# rev_n_v28.net
KiCad netlist of a schematic drawn in EAGLE
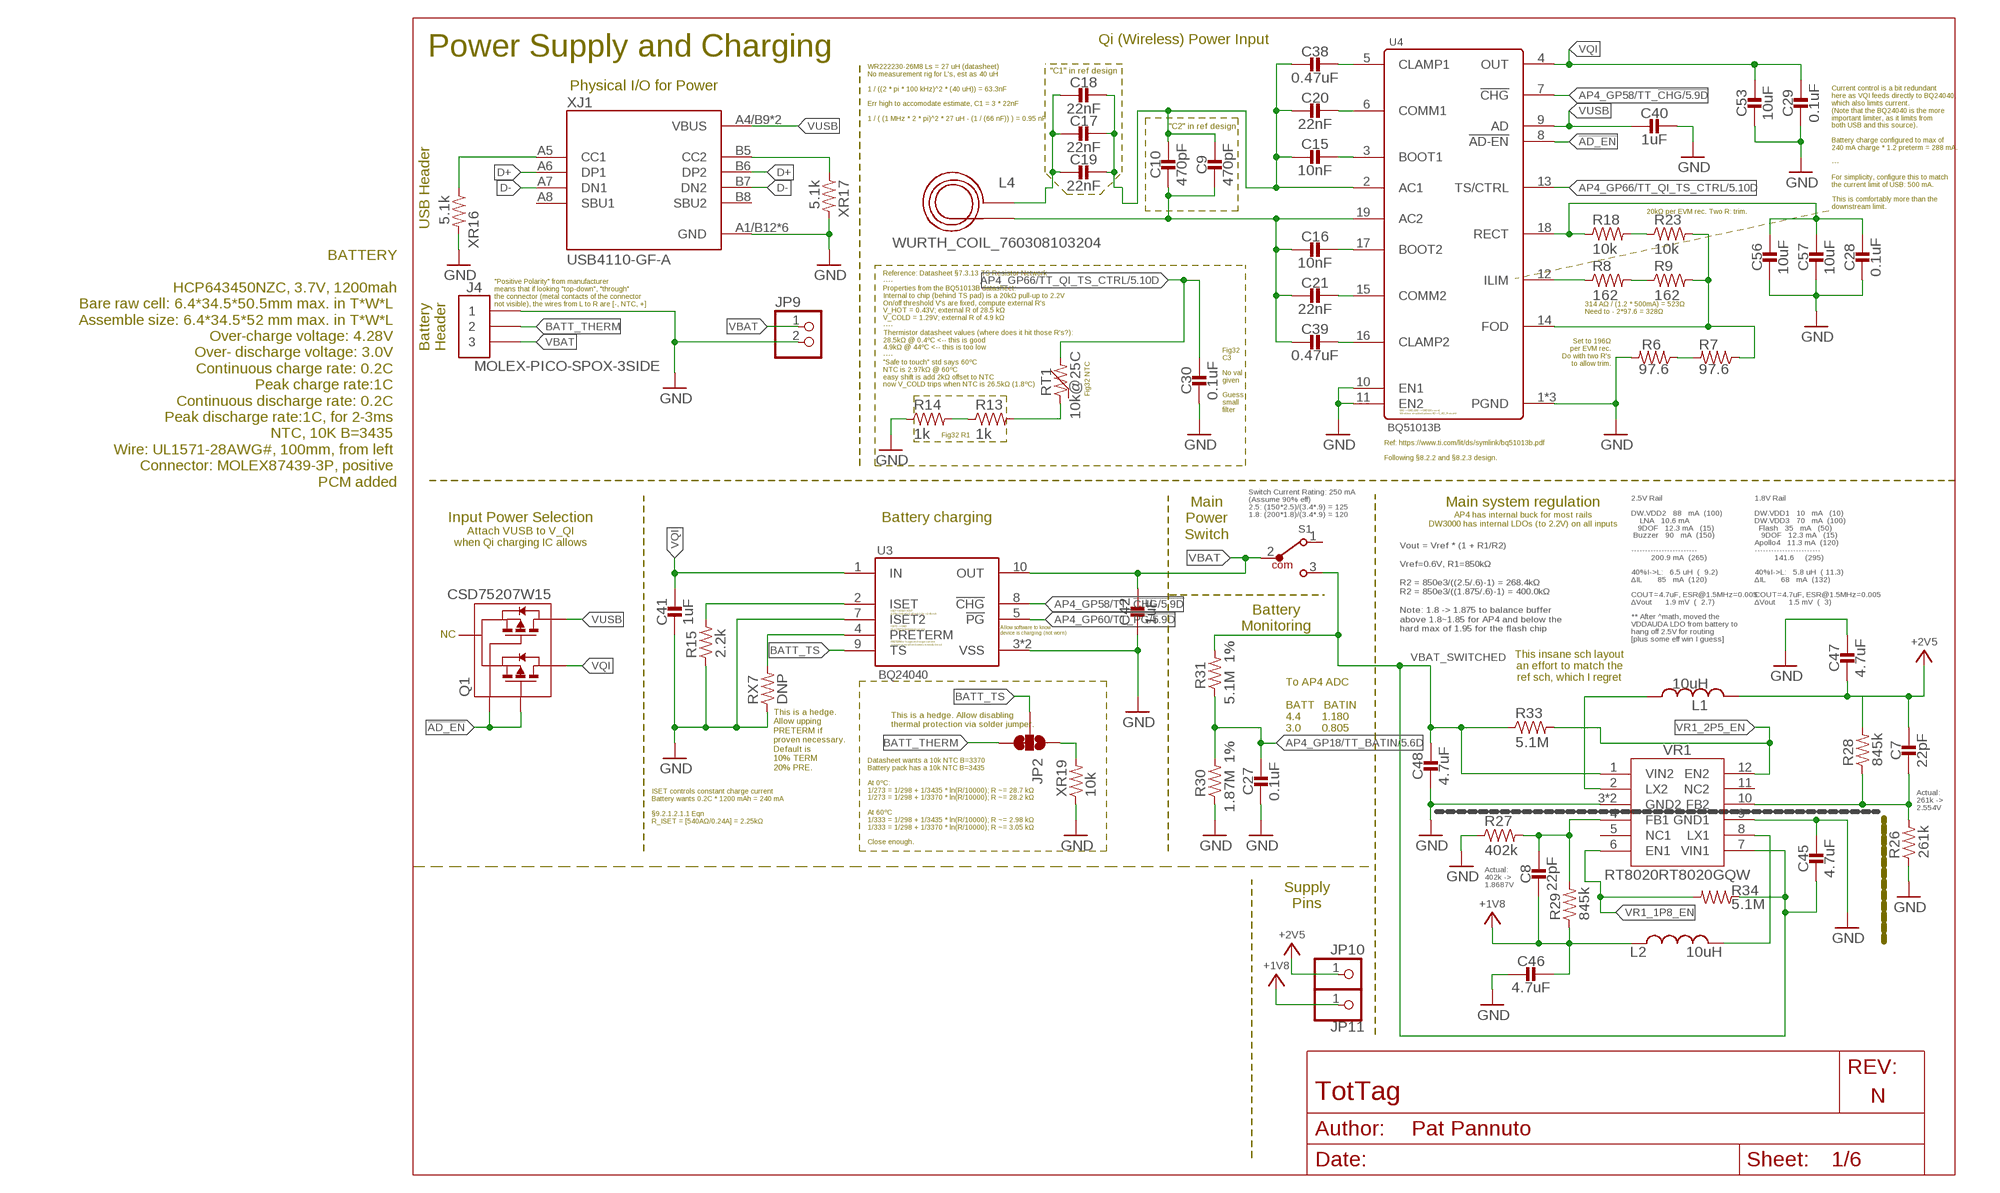
[diagram p0: schematic, sheet 1]
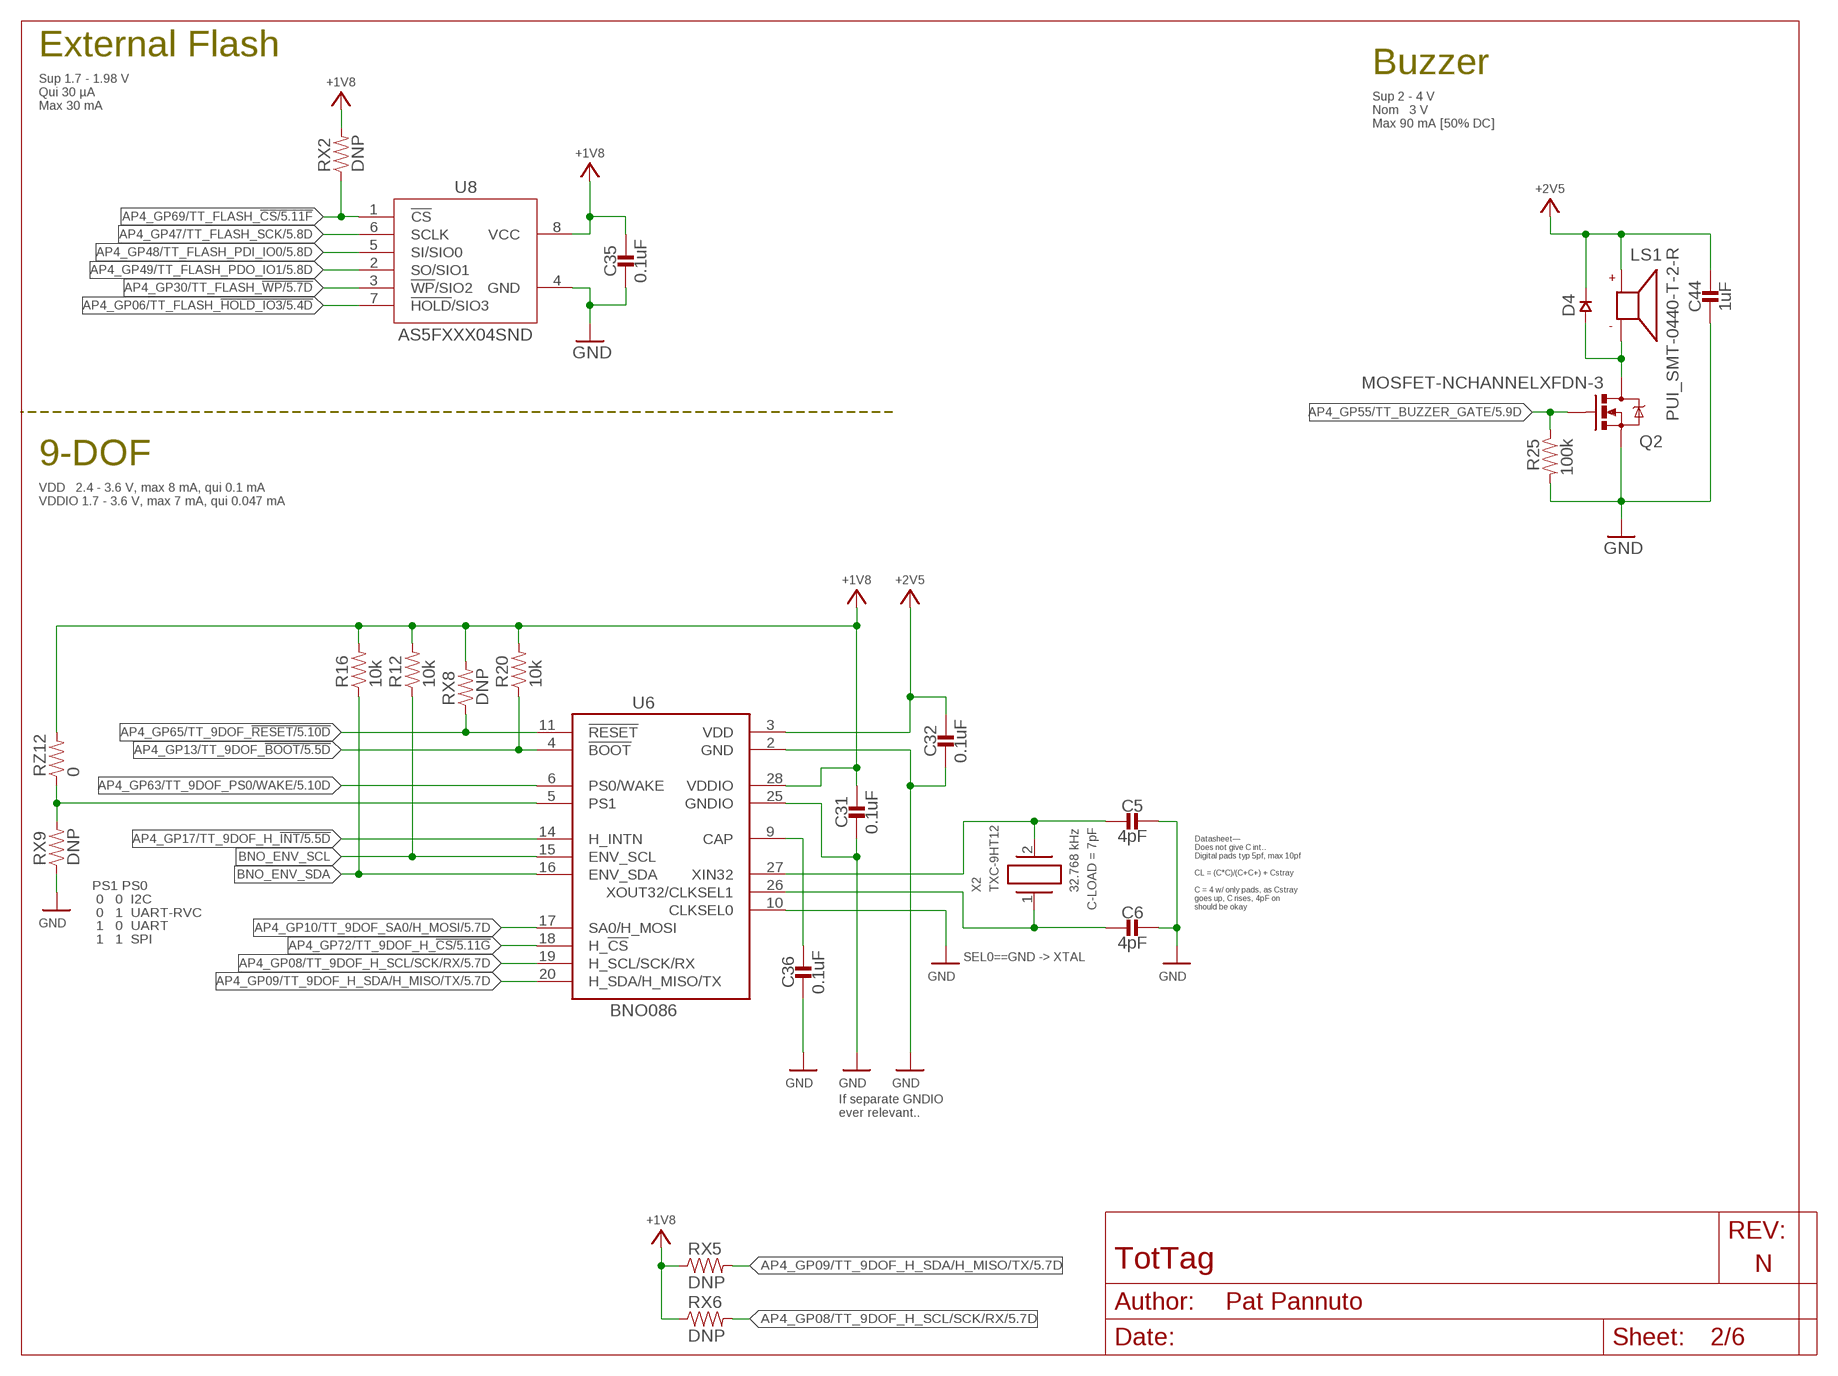
[diagram p1: schematic, sheet 2]
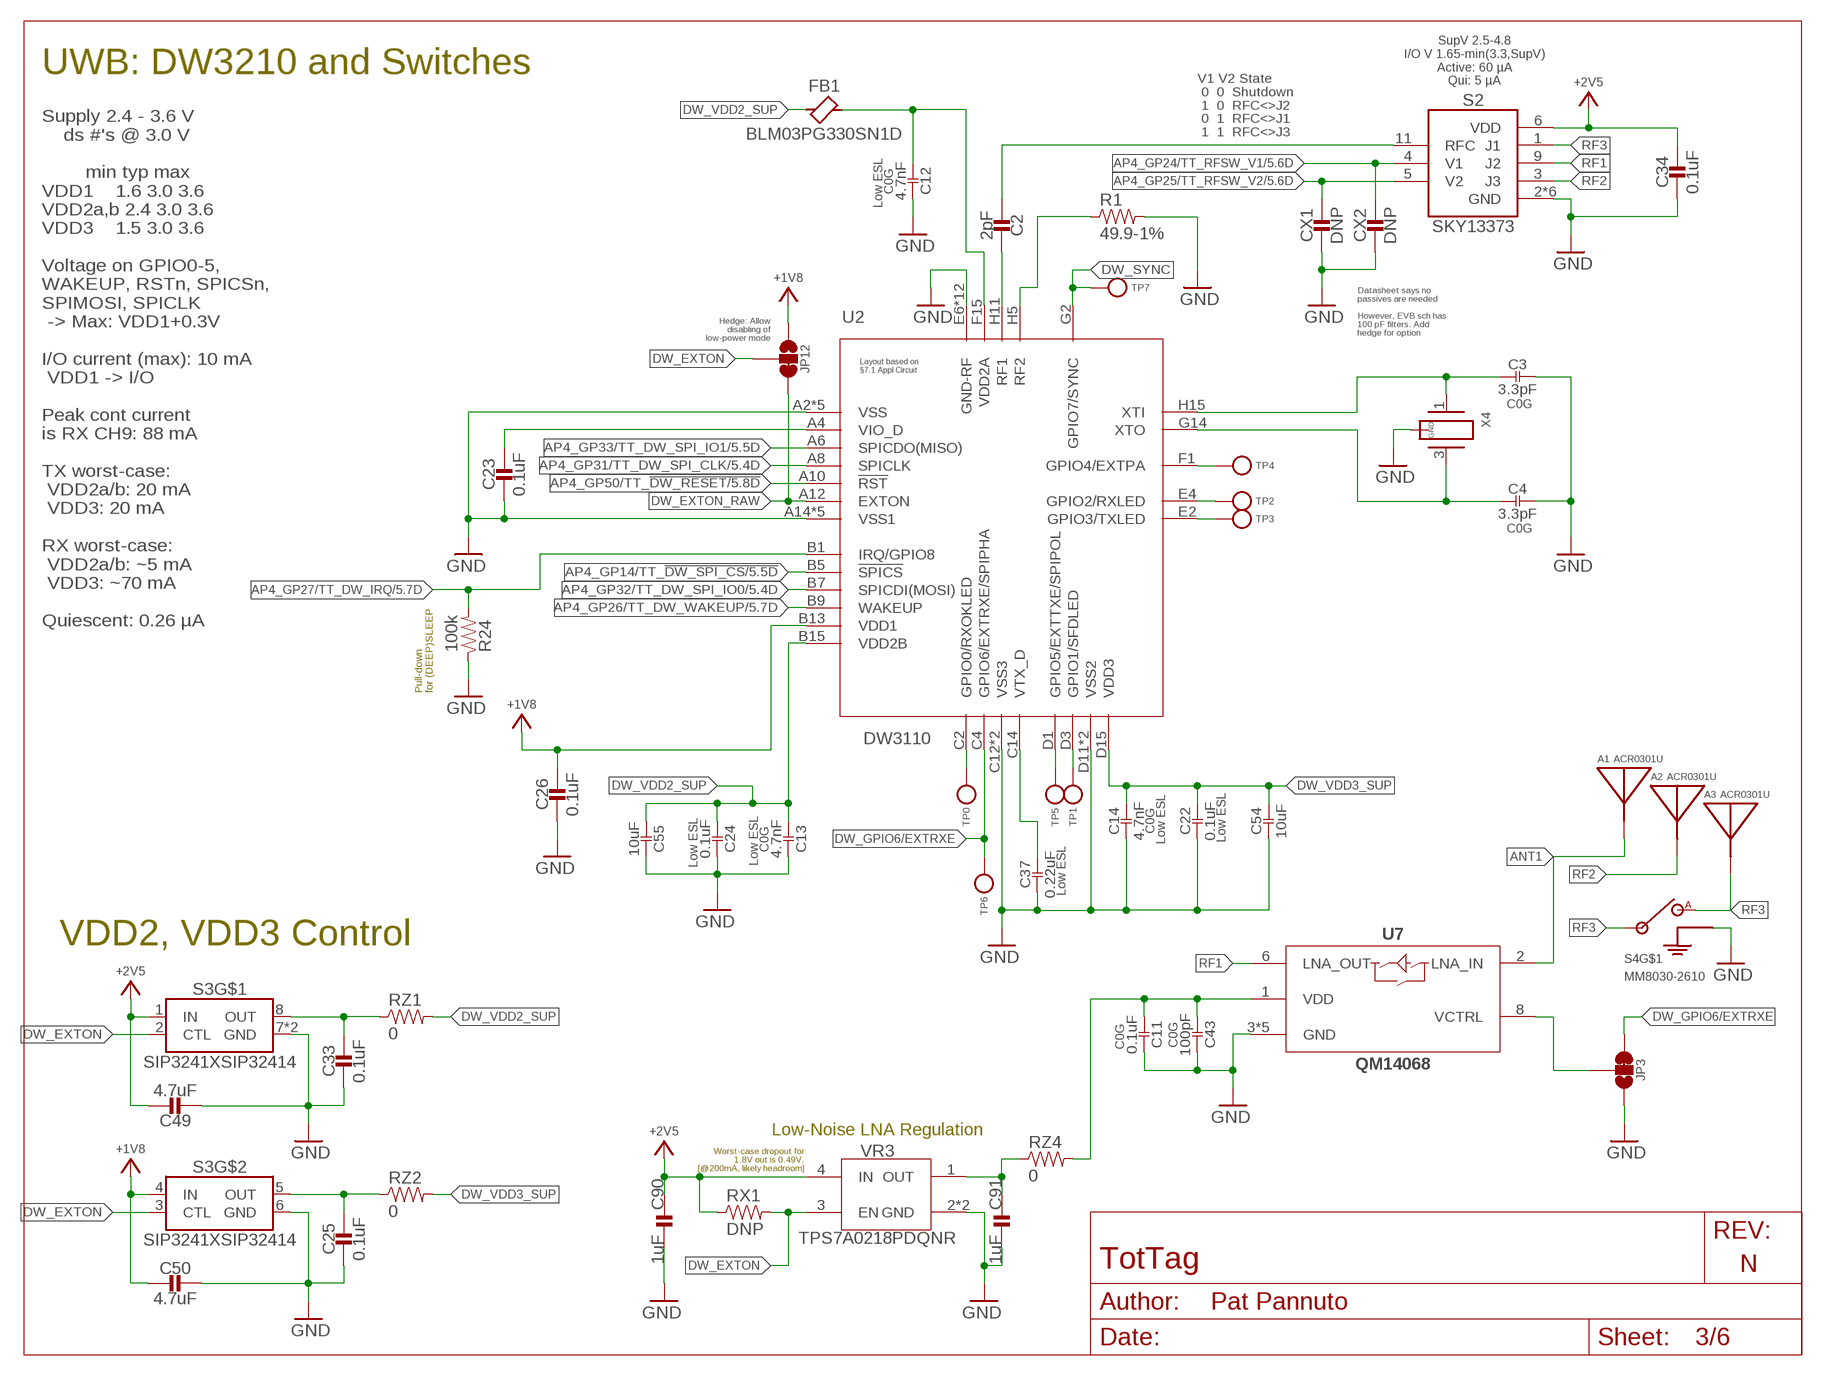
[diagram p2: schematic, sheet 3]
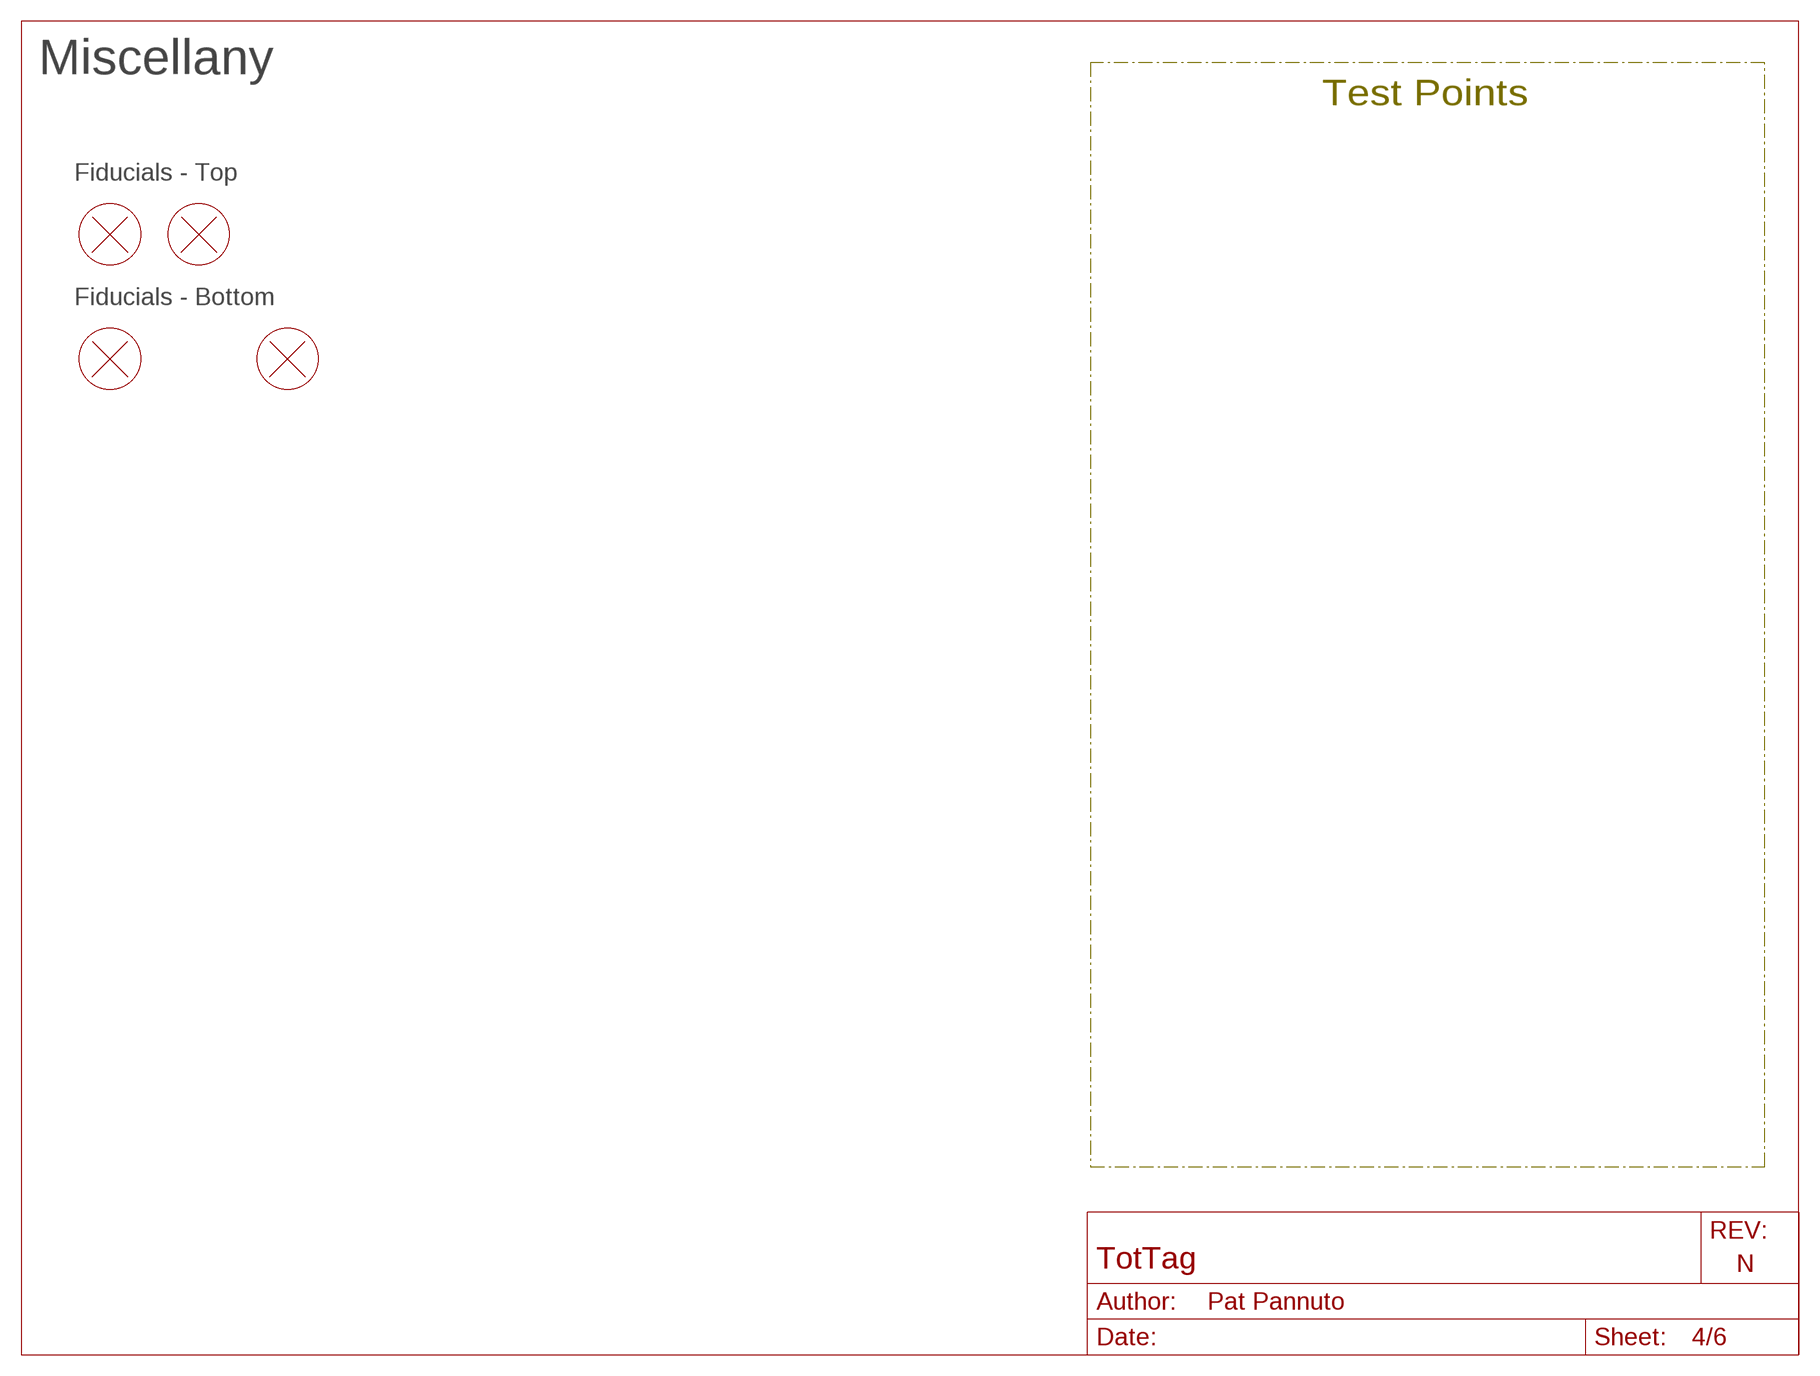
[diagram p3: schematic, sheet 4]
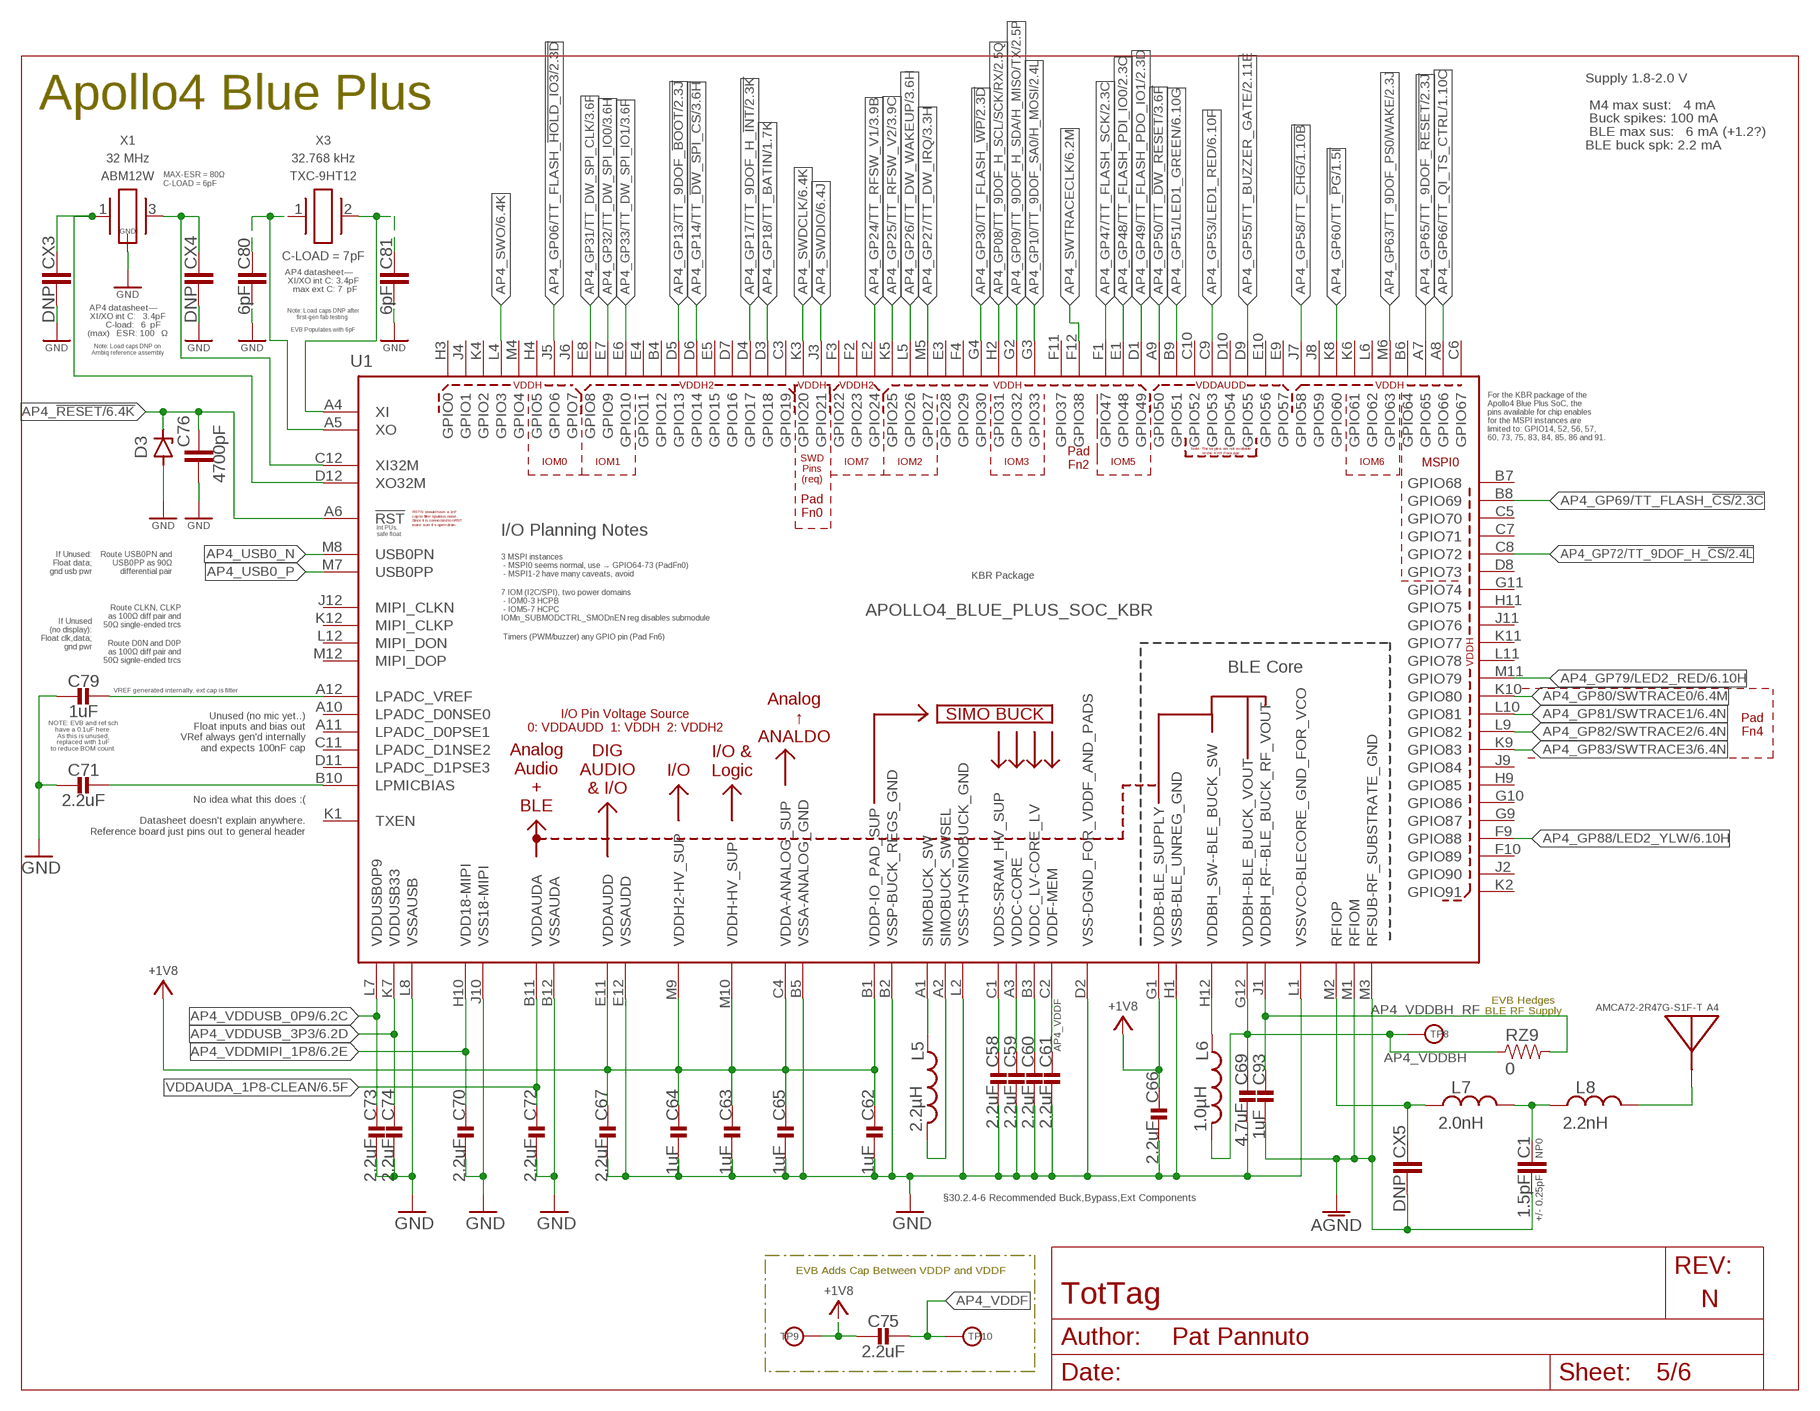
[diagram p4: schematic, sheet 5]
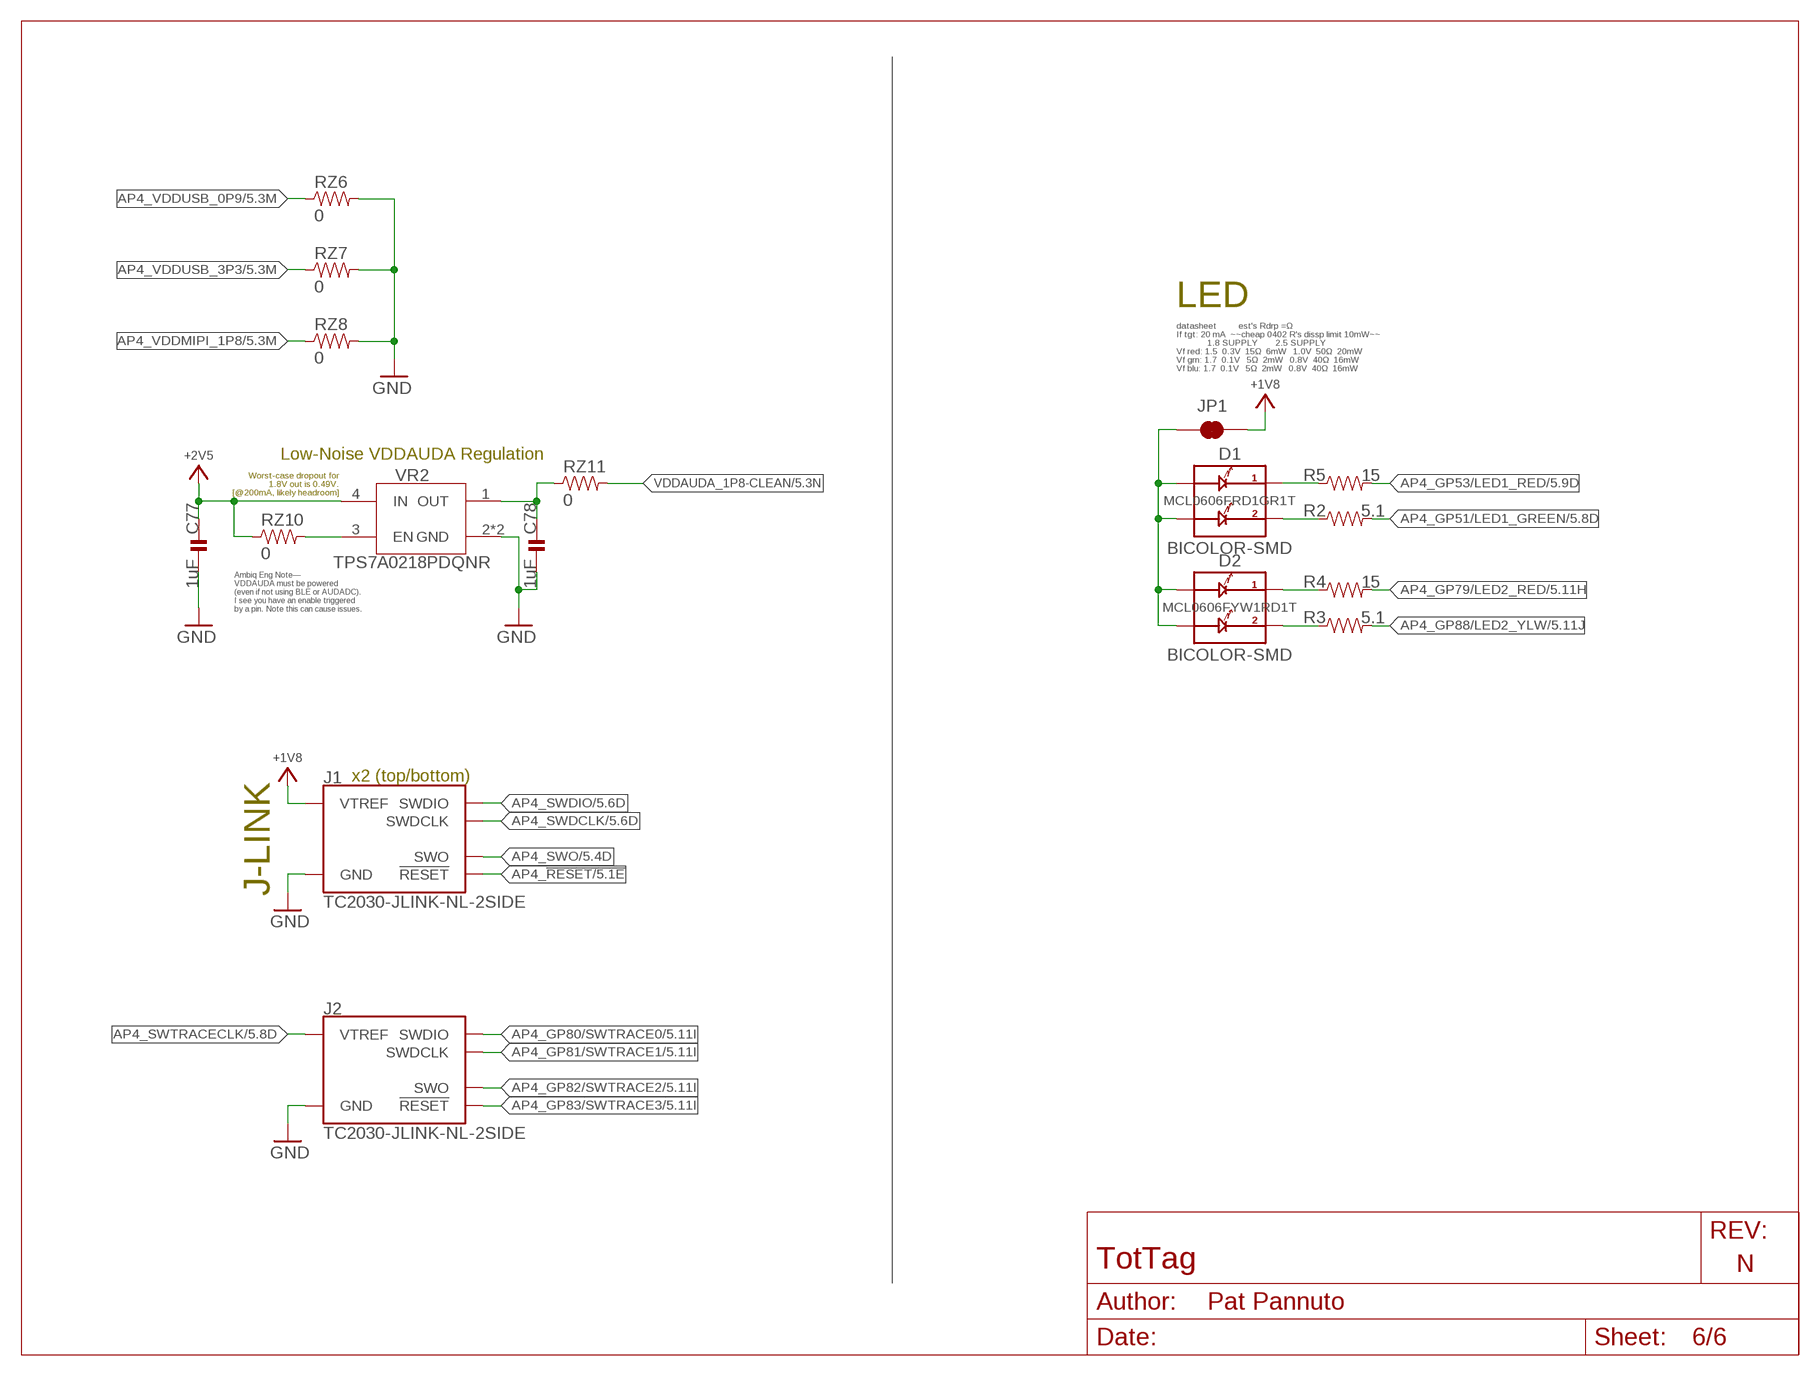
[diagram p5: schematic, sheet 6]

(export (version "E")
  (design (tool "Eeschema 10.0.6"))
  (components
    (comp (ref "A1")
      (value "ACR0301U")
      (footprint "eagle-import:ACR0301U")
      (fields (field (name "MANUFACTURER") "Abracon"))
      (libsource (lib "eagle-import") (part "ACR0301U"))
    )
    (comp (ref "A2")
      (value "ACR0301U")
      (footprint "eagle-import:ACR0301U")
      (fields (field (name "MANUFACTURER") "Abracon"))
      (libsource (lib "eagle-import") (part "ACR0301U"))
    )
    (comp (ref "A3")
      (value "ACR0301U")
      (footprint "eagle-import:ACR0301U")
      (fields (field (name "MANUFACTURER") "Abracon"))
      (libsource (lib "eagle-import") (part "ACR0301U"))
    )
    (comp (ref "C2")
      (value "2pF")
      (footprint "eagle-import:0201_CAP")
      (fields (field (name "MPN") "CBR02C209A5GAC"))
      (libsource (lib "eagle-import") (part "CAPACITOR0201_CAP"))
    )
    (comp (ref "C3")
      (value "3.3pF")
      (footprint "eagle-import:SMD_2012M-0805US-C")
      (fields
        (field (name "EIA") "C0G")
        (field (name "MANUFACTURER") "KYOCERA AVX")
        (field (name "MPN") "600F3R3BT250XT")
      )
      (libsource (lib "eagle-import") (part "C0805US"))
    )
    (comp (ref "C4")
      (value "3.3pF")
      (footprint "eagle-import:SMD_2012M-0805US-C")
      (fields
        (field (name "EIA") "C0G")
        (field (name "MANUFACTURER") "KYOCERA AVX")
        (field (name "MPN") "600F3R3BT250XT")
      )
      (libsource (lib "eagle-import") (part "C0805US"))
    )
    (comp (ref "C11")
      (value "0.1uF")
      (footprint "eagle-import:SMD_3216M-1206US-C")
      (fields (field (name "EIA") "C0G") (field (name "MPN") "GRM31C5C1H104JA01L"))
      (libsource (lib "eagle-import") (part "C1206US"))
    )
    (comp (ref "C12")
      (value "4.7nF")
      (footprint "eagle-import:SMD_1608M-0603US-C")
      (fields
        (field (name "EIA") "C0G")
        (field (name "FEATURES") "Low ESL")
        (field (name "MANUFACTURER") "KEMET")
        (field (name "MPN") "C0603C472J5GAC7867")
      )
      (libsource (lib "eagle-import") (part "C0603US"))
    )
    (comp (ref "C13")
      (value "4.7nF")
      (footprint "eagle-import:SMD_1608M-0603US-C")
      (fields
        (field (name "EIA") "C0G")
        (field (name "FEATURES") "Low ESL")
        (field (name "MANUFACTURER") "KEMET")
        (field (name "MPN") "C0603C472J5GAC7867")
      )
      (libsource (lib "eagle-import") (part "C0603US"))
    )
    (comp (ref "C14")
      (value "4.7nF")
      (footprint "eagle-import:SMD_1608M-0603US-C")
      (fields
        (field (name "EIA") "C0G")
        (field (name "FEATURES") "Low ESL")
        (field (name "MANUFACTURER") "KEMET")
        (field (name "MPN") "C0603C472J5GAC7867")
      )
      (libsource (lib "eagle-import") (part "C0603US"))
    )
    (comp (ref "C22")
      (value "0.1uF")
      (footprint "eagle-import:SMD_1608M-0603US-C")
      (fields (field (name "FEATURES") "Low ESL") (field (name "MPN") "C1608X7R1H104K080AA"))
      (libsource (lib "eagle-import") (part "C0603US"))
    )
    (comp (ref "C23")
      (value "0.1uF")
      (footprint "eagle-import:0402_CAP")
      (fields (field (name "MPN") "CL05A104KP5NNNC"))
      (libsource (lib "eagle-import") (part "passives_20904581_CAPACITOR0402_CAP"))
    )
    (comp (ref "C24")
      (value "0.1uF")
      (footprint "eagle-import:SMD_1608M-0603US-C")
      (fields (field (name "FEATURES") "Low ESL") (field (name "MPN") "C1608X7R1H104K080AA"))
      (libsource (lib "eagle-import") (part "C0603US"))
    )
    (comp (ref "C25")
      (value "0.1uF")
      (footprint "eagle-import:0402_CAP")
      (fields (field (name "MPN") "CL05A104KP5NNNC"))
      (libsource (lib "eagle-import") (part "passives_20904581_CAPACITOR0402_CAP"))
    )
    (comp (ref "C26")
      (value "0.1uF")
      (footprint "eagle-import:0402_CAP")
      (fields (field (name "MPN") "CL05A104KP5NNNC"))
      (libsource (lib "eagle-import") (part "passives_20904581_CAPACITOR0402_CAP"))
    )
    (comp (ref "C33")
      (value "0.1uF")
      (footprint "eagle-import:0402_CAP")
      (fields (field (name "MPN") "CL05A104KP5NNNC"))
      (libsource (lib "eagle-import") (part "passives_20904581_CAPACITOR0402_CAP"))
    )
    (comp (ref "C34")
      (value "0.1uF")
      (footprint "eagle-import:0402_CAP")
      (fields (field (name "MPN") "CL05A104KP5NNNC"))
      (libsource (lib "eagle-import") (part "passives_20904581_CAPACITOR0402_CAP"))
    )
    (comp (ref "C37")
      (value "0.22uF")
      (footprint "eagle-import:SMD_1608M-0603US-C")
      (fields (field (name "FEATURES") "Low ESL") (field (name "MPN") "C1608X7R1H224K080AB"))
      (libsource (lib "eagle-import") (part "C0603US"))
    )
    (comp (ref "C43")
      (value "100pF")
      (footprint "eagle-import:SMD_1005M-0402US-C")
      (fields (field (name "EIA") "C0G") (field (name "MPN") "C0402C101J3GACTU"))
      (libsource (lib "eagle-import") (part "C0402US"))
    )
    (comp (ref "C49")
      (value "4.7uF")
      (footprint "eagle-import:0603_CAP")
      (fields (field (name "MPN") "C1608X7S1A475K080AC"))
      (libsource (lib "eagle-import") (part "passives_20904581_CAPACITOR0603_CAP"))
    )
    (comp (ref "C50")
      (value "4.7uF")
      (footprint "eagle-import:0603_CAP")
      (fields (field (name "MPN") "C1608X7S1A475K080AC"))
      (libsource (lib "eagle-import") (part "passives_20904581_CAPACITOR0603_CAP"))
    )
    (comp (ref "C54")
      (value "10uF")
      (footprint "eagle-import:SMD_1608M-0603US-C")
      (fields (field (name "MPN") "CM105X5R106M25AT"))
      (libsource (lib "eagle-import") (part "C0603US"))
    )
    (comp (ref "C55")
      (value "10uF")
      (footprint "eagle-import:SMD_1608M-0603US-C")
      (fields (field (name "MPN") "CM105X5R106M25AT"))
      (libsource (lib "eagle-import") (part "C0603US"))
    )
    (comp (ref "C90")
      (value "1uF")
      (footprint "eagle-import:0201_CAP")
      (fields (field (name "MANUFACTURER") "Murata") (field (name "MPN") "GRM033R61A105ME44D"))
      (libsource (lib "eagle-import") (part "passives_20904581_CAPACITOR0201_CAP"))
    )
    (comp (ref "C91")
      (value "1uF")
      (footprint "eagle-import:0201_CAP")
      (fields (field (name "MANUFACTURER") "Murata") (field (name "MPN") "GRM033R61A105ME44D"))
      (libsource (lib "eagle-import") (part "passives_20904581_CAPACITOR0201_CAP"))
    )
    (comp (ref "CX1")
      (value "DNP")
      (footprint "eagle-import:0603_CAP")
      (libsource (lib "eagle-import") (part "passives_20904581_CAPACITOR0603_CAP"))
    )
    (comp (ref "CX2")
      (value "DNP")
      (footprint "eagle-import:0603_CAP")
      (libsource (lib "eagle-import") (part "passives_20904581_CAPACITOR0603_CAP"))
    )
    (comp (ref "FB1")
      (value "BLM03PG330SN1D")
      (footprint "eagle-import:0201_FB")
      (fields (field (name "MANUFACTURER") "Murata"))
      (libsource (lib "eagle-import") (part "FERRITE_BEAD0201"))
    )
    (comp (ref "JP3")
      (value "JUMPER-SMT_3_1-NC_TRACE_SILK")
      (footprint "eagle-import:SMT-JUMPER_3_1-NC_TRACE_SILK")
      (libsource (lib "eagle-import") (part "JUMPER-SMT_3_1-NC_TRACE_SILK"))
    )
    (comp (ref "JP12")
      (value "JUMPER-SMT_3_1-NC_TRACE_SILK")
      (footprint "eagle-import:SMT-JUMPER_3_1-NC_TRACE_SILK")
      (libsource (lib "eagle-import") (part "JUMPER-SMT_3_1-NC_TRACE_SILK"))
    )
    (comp (ref "R1")
      (value "49.9-1%")
      (footprint "eagle-import:0201_RES")
      (fields (field (name "MPN") "ERJ-1GNF49R9C"))
      (libsource (lib "eagle-import") (part "passives_20904581_RESISTOR0201_RES"))
    )
    (comp (ref "R24")
      (value "100k")
      (footprint "eagle-import:0402_RES")
      (fields (field (name "MPN") "RT0402BRE07100KL"))
      (libsource (lib "eagle-import") (part "RESISTOR0402_RES"))
    )
    (comp (ref "RX1")
      (value "DNP")
      (footprint "eagle-import:0603-RES")
      (libsource (lib "eagle-import") (part "passives_20904581_RESISTOR0603_RES"))
    )
    (comp (ref "RZ1")
      (value "0")
      (footprint "eagle-import:0603-RES")
      (fields (field (name "MPN") "RMCF0603ZT0R00"))
      (libsource (lib "eagle-import") (part "passives_20904581_RESISTOR0603_RES"))
    )
    (comp (ref "RZ2")
      (value "0")
      (footprint "eagle-import:0603-RES")
      (fields (field (name "MPN") "RMCF0603ZT0R00"))
      (libsource (lib "eagle-import") (part "passives_20904581_RESISTOR0603_RES"))
    )
    (comp (ref "RZ4")
      (value "0")
      (footprint "eagle-import:0402_RES")
      (fields (field (name "MPN") "RMCF0402ZT0R00"))
      (libsource (lib "eagle-import") (part "passives_20904581_RESISTOR0402_RES"))
    )
    (comp (ref "S2")
      (value "SKY13373")
      (footprint "eagle-import:SKY13373")
      (fields (field (name "MANUFACTURER") "Skyworks") (field (name "MPN") "SKY13373-460LF"))
      (libsource (lib "eagle-import") (part "SKY13373"))
    )
    (comp (ref "S3")
      (value "SIP3241XSIP32414")
      (footprint "eagle-import:TDFN2X2X0P6-8")
      (fields (field (name "MANUFACTURER") "Vishay") (field (name "MPN") "SIP32414DNP-T1-GE4"))
      (libsource (lib "eagle-import") (part "SIP3241XSIP32414"))
    )
    (comp (ref "S4")
      (value "MM8030-2610")
      (footprint "eagle-import:MM8030-2610")
      (fields (field (name "MANUFACTURER") "Murata"))
      (libsource (lib "eagle-import") (part "MM8030-2610"))
    )
    (comp (ref "TP0")
      (value "TEST-POINT")
      (footprint "eagle-import:PAD.03X.03")
      (libsource (lib "eagle-import") (part "TEST-POINT"))
    )
    (comp (ref "TP1")
      (value "TEST-POINT")
      (footprint "eagle-import:PAD.03X.03")
      (libsource (lib "eagle-import") (part "TEST-POINT"))
    )
    (comp (ref "TP2")
      (value "TEST-POINT")
      (footprint "eagle-import:PAD.03X.03")
      (libsource (lib "eagle-import") (part "TEST-POINT"))
    )
    (comp (ref "TP3")
      (value "TEST-POINT")
      (footprint "eagle-import:PAD.03X.03")
      (libsource (lib "eagle-import") (part "TEST-POINT"))
    )
    (comp (ref "TP4")
      (value "TEST-POINT")
      (footprint "eagle-import:PAD.03X.03")
      (libsource (lib "eagle-import") (part "TEST-POINT"))
    )
    (comp (ref "TP5")
      (value "TEST-POINT")
      (footprint "eagle-import:PAD.03X.03")
      (libsource (lib "eagle-import") (part "TEST-POINT"))
    )
    (comp (ref "TP6")
      (value "TEST-POINT")
      (footprint "eagle-import:PAD.03X.03")
      (libsource (lib "eagle-import") (part "TEST-POINT"))
    )
    (comp (ref "TP7")
      (value "TEST-POINT")
      (footprint "eagle-import:PAD.03X.03")
      (libsource (lib "eagle-import") (part "TEST-POINT"))
    )
    (comp (ref "U2")
      (value "DW3110")
      (footprint "eagle-import:WLCSP52")
      (fields (field (name "MANUFACTURER") "Qorvo"))
      (libsource (lib "eagle-import") (part "DW3110"))
    )
    (comp (ref "U7")
      (value "QM14068")
      (footprint "eagle-import:QM14068")
      (fields (field (name "MANUFACTURER") "Qorvo"))
      (libsource (lib "eagle-import") (part "QM14068"))
    )
    (comp (ref "VR3")
      (value "TPS7A0218PDQNR")
      (footprint "eagle-import:4-XDFN-EP")
      (libsource (lib "eagle-import") (part "TPS7A0218PDQNR"))
    )
    (comp (ref "X4")
      (value "TXC-8Y")
      (footprint "eagle-import:TXC-8Y")
      (libsource (lib "eagle-import") (part "TXC-8Y"))
    )
    (comp (ref "C5")
      (value "4pF")
      (footprint "eagle-import:0201_CAP")
      (fields (field (name "MANUFACTURER") "Murata") (field (name "MPN") "GRM0335C1H4R0BA01D"))
      (libsource (lib "eagle-import") (part "passives_20904581_CAPACITOR0201_CAP"))
    )
    (comp (ref "C6")
      (value "4pF")
      (footprint "eagle-import:0201_CAP")
      (fields (field (name "MANUFACTURER") "Murata") (field (name "MPN") "GRM0335C1H4R0BA01D"))
      (libsource (lib "eagle-import") (part "passives_20904581_CAPACITOR0201_CAP"))
    )
    (comp (ref "C31")
      (value "0.1uF")
      (footprint "eagle-import:0402_CAP")
      (fields (field (name "MPN") "CL05A104KP5NNNC"))
      (libsource (lib "eagle-import") (part "passives_20904581_CAPACITOR0402_CAP"))
    )
    (comp (ref "C32")
      (value "0.1uF")
      (footprint "eagle-import:0402_CAP")
      (fields (field (name "MPN") "CL05A104KP5NNNC"))
      (libsource (lib "eagle-import") (part "passives_20904581_CAPACITOR0402_CAP"))
    )
    (comp (ref "C35")
      (value "0.1uF")
      (footprint "eagle-import:0402_CAP")
      (fields (field (name "MPN") "CL05A104KP5NNNC"))
      (libsource (lib "eagle-import") (part "passives_20904581_CAPACITOR0402_CAP"))
    )
    (comp (ref "C36")
      (value "0.1uF")
      (footprint "eagle-import:0402_CAP")
      (fields (field (name "MPN") "CL05A104KP5NNNC"))
      (libsource (lib "eagle-import") (part "CAPACITOR0402_CAP"))
    )
    (comp (ref "C44")
      (value "1uF")
      (footprint "eagle-import:0402_CAP")
      (fields (field (name "MPN") "GRM155R70J105KA12J"))
      (libsource (lib "eagle-import") (part "CAPACITOR0402_CAP"))
    )
    (comp (ref "D4")
      (value "DIODE0402")
      (footprint "eagle-import:0402_DIODE")
      (fields (field (name "MPN") "CDSQR400B-HF"))
      (libsource (lib "eagle-import") (part "DIODE0402"))
    )
    (comp (ref "LS1")
      (value "PUI_SMT-0440-T-2-R")
      (footprint "eagle-import:SMT-0440-T-2-R")
      (fields (field (name "MPN") "SMT-0440-T-2-R"))
      (libsource (lib "eagle-import") (part "PUI_SMT-0440-T-2-R"))
    )
    (comp (ref "Q2")
      (value "MOSFET-NCHANNELXFDN-3")
      (footprint "eagle-import:XFDFN-3")
      (libsource (lib "eagle-import") (part "MOSFET-NCHANNELXFDN-3"))
    )
    (comp (ref "R12")
      (value "10k")
      (footprint "eagle-import:0402_RES")
      (fields (field (name "MPN") "RC0402JR-0710KL"))
      (libsource (lib "eagle-import") (part "RESISTOR0402_RES"))
    )
    (comp (ref "R16")
      (value "10k")
      (footprint "eagle-import:0402_RES")
      (fields (field (name "MPN") "RC0402JR-0710KL"))
      (libsource (lib "eagle-import") (part "RESISTOR0402_RES"))
    )
    (comp (ref "R20")
      (value "10k")
      (footprint "eagle-import:0402_RES")
      (fields (field (name "MPN") "RC0402JR-0710KL"))
      (libsource (lib "eagle-import") (part "RESISTOR0402_RES"))
    )
    (comp (ref "R25")
      (value "100k")
      (footprint "eagle-import:0402_RES")
      (fields (field (name "MPN") "RT0402BRE07100KL"))
      (libsource (lib "eagle-import") (part "RESISTOR0402_RES"))
    )
    (comp (ref "RX2")
      (value "DNP")
      (footprint "eagle-import:0603-RES")
      (libsource (lib "eagle-import") (part "passives_20904581_RESISTOR0603_RES"))
    )
    (comp (ref "RX5")
      (value "DNP")
      (footprint "eagle-import:0603-RES")
      (libsource (lib "eagle-import") (part "passives_20904581_RESISTOR0603_RES"))
    )
    (comp (ref "RX6")
      (value "DNP")
      (footprint "eagle-import:0603-RES")
      (libsource (lib "eagle-import") (part "passives_20904581_RESISTOR0603_RES"))
    )
    (comp (ref "RX8")
      (value "DNP")
      (footprint "eagle-import:0603-RES")
      (libsource (lib "eagle-import") (part "passives_20904581_RESISTOR0603_RES"))
    )
    (comp (ref "RX9")
      (value "DNP")
      (footprint "eagle-import:0603-RES")
      (libsource (lib "eagle-import") (part "passives_20904581_RESISTOR0603_RES"))
    )
    (comp (ref "RZ12")
      (value "0")
      (footprint "eagle-import:0402_RES")
      (fields (field (name "MPN") "RMCF0402ZT0R00"))
      (libsource (lib "eagle-import") (part "passives_20904581_RESISTOR0402_RES"))
    )
    (comp (ref "U6")
      (value "BNO086")
      (footprint "eagle-import:LGA28R0P510X4_5P2X3P8X1")
      (fields (field (name "MANUFACTURER") "CEVA Technologies, Inc."))
      (libsource (lib "eagle-import") (part "BNO086"))
    )
    (comp (ref "U8")
      (value "AS5FXXX04SND")
      (footprint "eagle-import:AS5FXXXXXXXX-XXLXN")
      (fields (field (name "MANUFACTURER") "Alliance Memory") (field (name "MPN") "AS5F18G04SND-10LIN"))
      (libsource (lib "eagle-import") (part "AS5FXXX04SND"))
    )
    (comp (ref "X2")
      (value "TXC-9HT12")
      (footprint "eagle-import:TXC-9HT12")
      (fields
        (field (name "C-LOAD") "7pF")
        (field (name "FREQUENCY") "32.768 kHz")
        (field (name "MANUFACTURER") "TXC Corp")
        (field (name "MPN") "9HT12-32.768KDZY-T")
      )
      (libsource (lib "eagle-import") (part "TXC-9HT12"))
    )
    (comp (ref "C77")
      (value "1uF")
      (footprint "eagle-import:0201_CAP")
      (fields (field (name "MANUFACTURER") "Murata") (field (name "MPN") "GRM033R61A105ME44D"))
      (libsource (lib "eagle-import") (part "passives_20904581_CAPACITOR0201_CAP"))
    )
    (comp (ref "C78")
      (value "1uF")
      (footprint "eagle-import:0201_CAP")
      (fields (field (name "MANUFACTURER") "Murata") (field (name "MPN") "GRM033R61A105ME44D"))
      (libsource (lib "eagle-import") (part "passives_20904581_CAPACITOR0201_CAP"))
    )
    (comp (ref "D1")
      (value "BICOLOR-SMD")
      (footprint "eagle-import:LED-0606")
      (fields (field (name "MPN") "MCL0606FRD1GR1T"))
      (libsource (lib "eagle-import") (part "BICOLOR-SMD"))
    )
    (comp (ref "D2")
      (value "BICOLOR-SMD")
      (footprint "eagle-import:LED-0606")
      (fields (field (name "MPN") "MCL0606FYW1RD1T"))
      (libsource (lib "eagle-import") (part "BICOLOR-SMD"))
    )
    (comp (ref "J1")
      (value "TC2030-JLINK-NL-2SIDE")
      (footprint "eagle-import:TC2030-IDC-NL-2SIDE")
      (libsource (lib "eagle-import") (part "TC2030-JLINK-NL-2SIDE"))
    )
    (comp (ref "J2")
      (value "TC2030-JLINK-NL-2SIDE")
      (footprint "eagle-import:TC2030-IDC-NL-2SIDE")
      (libsource (lib "eagle-import") (part "TC2030-JLINK-NL-2SIDE"))
    )
    (comp (ref "JP1")
      (value "JUMPER-SMT_2_NC_TRACE_SILK")
      (footprint "eagle-import:SMT-JUMPER_2_NC_TRACE_SILK")
      (libsource (lib "eagle-import") (part "JUMPER-SMT_2_NC_TRACE_SILK"))
    )
    (comp (ref "R2")
      (value "5.1")
      (footprint "eagle-import:0402_RES")
      (fields (field (name "MPN") "RC0402JR-075R1L"))
      (libsource (lib "eagle-import") (part "RESISTOR0402_RES"))
    )
    (comp (ref "R3")
      (value "5.1")
      (footprint "eagle-import:0402_RES")
      (fields (field (name "MPN") "RC0402JR-075R1L"))
      (libsource (lib "eagle-import") (part "RESISTOR0402_RES"))
    )
    (comp (ref "R4")
      (value "15")
      (footprint "eagle-import:0402_RES")
      (fields (field (name "MPN") "RC0402JR-0715RL"))
      (libsource (lib "eagle-import") (part "RESISTOR0402_RES"))
    )
    (comp (ref "R5")
      (value "15")
      (footprint "eagle-import:0402_RES")
      (fields (field (name "MPN") "RC0402JR-0715RL"))
      (libsource (lib "eagle-import") (part "RESISTOR0402_RES"))
    )
    (comp (ref "RZ6")
      (value "0")
      (footprint "eagle-import:0402_RES")
      (fields (field (name "MPN") "RMCF0402ZT0R00"))
      (libsource (lib "eagle-import") (part "passives_20904581_RESISTOR0402_RES"))
    )
    (comp (ref "RZ7")
      (value "0")
      (footprint "eagle-import:0402_RES")
      (fields (field (name "MPN") "RMCF0402ZT0R00"))
      (libsource (lib "eagle-import") (part "passives_20904581_RESISTOR0402_RES"))
    )
    (comp (ref "RZ8")
      (value "0")
      (footprint "eagle-import:0402_RES")
      (fields (field (name "MPN") "RMCF0402ZT0R00"))
      (libsource (lib "eagle-import") (part "passives_20904581_RESISTOR0402_RES"))
    )
    (comp (ref "RZ10")
      (value "0")
      (footprint "eagle-import:0402_RES")
      (fields (field (name "MPN") "RMCF0402ZT0R00"))
      (libsource (lib "eagle-import") (part "passives_20904581_RESISTOR0402_RES"))
    )
    (comp (ref "RZ11")
      (value "0")
      (footprint "eagle-import:0402_RES")
      (fields (field (name "MPN") "RMCF0402ZT0R00"))
      (libsource (lib "eagle-import") (part "passives_20904581_RESISTOR0402_RES"))
    )
    (comp (ref "VR2")
      (value "TPS7A0218PDQNR")
      (footprint "eagle-import:4-XDFN-EP")
      (libsource (lib "eagle-import") (part "TPS7A0218PDQNR"))
    )
    (comp (ref "FD1")
      (value "FIDUCIAL")
      (footprint "eagle-import:FIDUCIAL_1MM-CU_2MM-MASK")
      (libsource (lib "eagle-import") (part "FIDUCIAL"))
    )
    (comp (ref "FD2")
      (value "FIDUCIAL")
      (footprint "eagle-import:FIDUCIAL_1MM-CU_2MM-MASK")
      (libsource (lib "eagle-import") (part "FIDUCIAL"))
    )
    (comp (ref "FD4")
      (value "FIDUCIAL")
      (footprint "eagle-import:FIDUCIAL_1MM-CU_2MM-MASK")
      (libsource (lib "eagle-import") (part "FIDUCIAL"))
    )
    (comp (ref "FD6")
      (value "FIDUCIAL")
      (footprint "eagle-import:FIDUCIAL_1MM-CU_2MM-MASK")
      (libsource (lib "eagle-import") (part "FIDUCIAL"))
    )
    (comp (ref "C7")
      (value "22pF")
      (footprint "eagle-import:0201_CAP")
      (fields (field (name "MPN") "GRM0335C1H220FA01D"))
      (libsource (lib "eagle-import") (part "passives_20904581_CAPACITOR0201_CAP"))
    )
    (comp (ref "C8")
      (value "22pF")
      (footprint "eagle-import:0201_CAP")
      (fields (field (name "MPN") "GRM0335C1H220FA01D"))
      (libsource (lib "eagle-import") (part "passives_20904581_CAPACITOR0201_CAP"))
    )
    (comp (ref "C9")
      (value "470pF")
      (footprint "eagle-import:0402_CAP")
      (description "CAP CER 470PF 50V C0G/NP0 0402")
      (fields (field (name "MANUFACTURER") "Murata") (field (name "MPN") "GRM1555C1H471JA01J"))
      (libsource (lib "eagle-import") (part "passives_20904581_CAPACITOR0402_CAP"))
    )
    (comp (ref "C10")
      (value "470pF")
      (footprint "eagle-import:0402_CAP")
      (description "CAP CER 470PF 50V C0G/NP0 0402")
      (fields (field (name "MANUFACTURER") "Murata") (field (name "MPN") "GRM1555C1H471JA01J"))
      (libsource (lib "eagle-import") (part "passives_20904581_CAPACITOR0402_CAP"))
    )
    (comp (ref "C15")
      (value "10nF")
      (footprint "eagle-import:0402_CAP")
      (fields (field (name "MPN") "GRM155R71H103KA88J"))
      (libsource (lib "eagle-import") (part "passives_20904581_CAPACITOR0402_CAP"))
    )
    (comp (ref "C16")
      (value "10nF")
      (footprint "eagle-import:0402_CAP")
      (fields (field (name "MPN") "GRM155R71H103KA88J"))
      (libsource (lib "eagle-import") (part "passives_20904581_CAPACITOR0402_CAP"))
    )
    (comp (ref "C17")
      (value "22nF")
      (footprint "eagle-import:0402_CAP")
      (fields (field (name "MPN") "GRM155R71E223JA61D"))
      (libsource (lib "eagle-import") (part "passives_20904581_CAPACITOR0402_CAP"))
    )
    (comp (ref "C18")
      (value "22nF")
      (footprint "eagle-import:0402_CAP")
      (fields (field (name "MPN") "GRM155R71E223JA61D"))
      (libsource (lib "eagle-import") (part "passives_20904581_CAPACITOR0402_CAP"))
    )
    (comp (ref "C19")
      (value "22nF")
      (footprint "eagle-import:0402_CAP")
      (fields (field (name "MPN") "GRM155R71E223JA61D"))
      (libsource (lib "eagle-import") (part "passives_20904581_CAPACITOR0402_CAP"))
    )
    (comp (ref "C20")
      (value "22nF")
      (footprint "eagle-import:0402_CAP")
      (fields (field (name "MPN") "CC0402ZRY5V8BB223"))
      (libsource (lib "eagle-import") (part "passives_20904581_CAPACITOR0402_CAP"))
    )
    (comp (ref "C21")
      (value "22nF")
      (footprint "eagle-import:0402_CAP")
      (fields (field (name "MPN") "CC0402ZRY5V8BB223"))
      (libsource (lib "eagle-import") (part "passives_20904581_CAPACITOR0402_CAP"))
    )
    (comp (ref "C27")
      (value "0.1uF")
      (footprint "eagle-import:0402_CAP")
      (fields (field (name "MPN") "GRM155R71C104KA88J "))
      (libsource (lib "eagle-import") (part "CAPACITOR0402_CAP"))
    )
    (comp (ref "C28")
      (value "0.1uF")
      (footprint "eagle-import:0402_CAP")
      (fields (field (name "MPN") "GRM155R71C104KA88J "))
      (libsource (lib "eagle-import") (part "CAPACITOR0402_CAP"))
    )
    (comp (ref "C29")
      (value "0.1uF")
      (footprint "eagle-import:0402_CAP")
      (fields (field (name "MPN") "GRM155R71C104KA88J "))
      (libsource (lib "eagle-import") (part "CAPACITOR0402_CAP"))
    )
    (comp (ref "C30")
      (value "0.1uF")
      (footprint "eagle-import:0402_CAP")
      (fields (field (name "MPN") "GRM155R71C104KA88J "))
      (libsource (lib "eagle-import") (part "CAPACITOR0402_CAP"))
    )
    (comp (ref "C38")
      (value "0.47uF")
      (footprint "eagle-import:0402_CAP")
      (fields (field (name "MPN") "GRT155R61E474ME01D"))
      (libsource (lib "eagle-import") (part "passives_20904581_CAPACITOR0402_CAP"))
    )
    (comp (ref "C39")
      (value "0.47uF")
      (footprint "eagle-import:0402_CAP")
      (fields (field (name "MPN") "GRT155R61E474ME01D"))
      (libsource (lib "eagle-import") (part "passives_20904581_CAPACITOR0402_CAP"))
    )
    (comp (ref "C40")
      (value "1uF")
      (footprint "eagle-import:0402_CAP")
      (fields (field (name "MPN") "GRM155R70J105KA12J"))
      (libsource (lib "eagle-import") (part "CAPACITOR0402_CAP"))
    )
    (comp (ref "C41")
      (value "1uF")
      (footprint "eagle-import:0402_CAP")
      (fields (field (name "MPN") "GRM155R70J105KA12J"))
      (libsource (lib "eagle-import") (part "CAPACITOR0402_CAP"))
    )
    (comp (ref "C42")
      (value "1uF")
      (footprint "eagle-import:0402_CAP")
      (fields (field (name "MPN") "GRM155R70J105KA12J"))
      (libsource (lib "eagle-import") (part "CAPACITOR0402_CAP"))
    )
    (comp (ref "C45")
      (value "4.7uF")
      (footprint "eagle-import:0603_CAP")
      (fields (field (name "MPN") "C1608X7S1A475K080AC"))
      (libsource (lib "eagle-import") (part "passives_20904581_CAPACITOR0603_CAP"))
    )
    (comp (ref "C46")
      (value "4.7uF")
      (footprint "eagle-import:0603_CAP")
      (fields (field (name "MPN") "C1608X7S1A475K080AC"))
      (libsource (lib "eagle-import") (part "passives_20904581_CAPACITOR0603_CAP"))
    )
    (comp (ref "C47")
      (value "4.7uF")
      (footprint "eagle-import:0603_CAP")
      (fields (field (name "MPN") "C1608X7S1A475K080AC"))
      (libsource (lib "eagle-import") (part "passives_20904581_CAPACITOR0603_CAP"))
    )
    (comp (ref "C48")
      (value "4.7uF")
      (footprint "eagle-import:0603_CAP")
      (fields (field (name "MPN") "C1608X7S1A475K080AC"))
      (libsource (lib "eagle-import") (part "passives_20904581_CAPACITOR0603_CAP"))
    )
    (comp (ref "C53")
      (value "10uF")
      (footprint "eagle-import:0603_CAP")
      (fields (field (name "MPN") "CM105X5R106M25AT"))
      (libsource (lib "eagle-import") (part "passives_20904581_CAPACITOR0603_CAP"))
    )
    (comp (ref "C56")
      (value "10uF")
      (footprint "eagle-import:0603_CAP")
      (fields (field (name "MPN") "CM105X5R106M25AT"))
      (libsource (lib "eagle-import") (part "passives_20904581_CAPACITOR0603_CAP"))
    )
    (comp (ref "C57")
      (value "10uF")
      (footprint "eagle-import:0603_CAP")
      (fields (field (name "MPN") "CM105X5R106M25AT"))
      (libsource (lib "eagle-import") (part "passives_20904581_CAPACITOR0603_CAP"))
    )
    (comp (ref "J4")
      (value "MOLEX-PICO-SPOX-3SIDE")
      (footprint "eagle-import:MOLEX-PICO-SPOX-3_SIDE")
      (libsource (lib "eagle-import") (part "MOLEX-PICO-SPOX-3SIDE"))
    )
    (comp (ref "JP2")
      (value "JUMPER-SMT_3_1-NC_TRACE_SILK")
      (footprint "eagle-import:SMT-JUMPER_3_1-NC_TRACE_SILK")
      (libsource (lib "eagle-import") (part "JUMPER-SMT_3_1-NC_TRACE_SILK"))
    )
    (comp (ref "JP9")
      (value "PINHD-1X2")
      (footprint "eagle-import:1X02")
      (libsource (lib "eagle-import") (part "PINHD-1X2"))
    )
    (comp (ref "JP10")
      (value "PINHD-1X1")
      (footprint "eagle-import:1X01")
      (libsource (lib "eagle-import") (part "PINHD-1X1"))
    )
    (comp (ref "JP11")
      (value "PINHD-1X1")
      (footprint "eagle-import:1X01")
      (libsource (lib "eagle-import") (part "PINHD-1X1"))
    )
    (comp (ref "L1")
      (value "10uH")
      (footprint "eagle-import:NRX3015")
      (fields (field (name "MANUFACTURER") "TAIYO YUDEN") (field (name "MPN") "NR3015T100M"))
      (libsource (lib "eagle-import") (part "INDUCTORNRX3015"))
    )
    (comp (ref "L2")
      (value "10uH")
      (footprint "eagle-import:NRX3015")
      (fields (field (name "MANUFACTURER") "TAIYO YUDEN") (field (name "MPN") "NR3015T100M"))
      (libsource (lib "eagle-import") (part "INDUCTORNRX3015"))
    )
    (comp (ref "L4")
      (value "WURTH_COIL_760308103204")
      (footprint "eagle-import:WURTH_COIL_760308103204")
      (fields (field (name "MANUFACTURER") "Würth Elektronik") (field (name "MPN") "760308103204"))
      (libsource (lib "eagle-import") (part "WURTH_COIL_760308103204"))
    )
    (comp (ref "Q1")
      (value "CSD75207W15")
      (footprint "eagle-import:DSBGA")
      (fields (field (name "MANUFACTURER") "TEXAS INSTRUMENTS"))
      (libsource (lib "eagle-import") (part "CSD75207W15"))
    )
    (comp (ref "R6")
      (value "97.6")
      (footprint "eagle-import:0402_RES")
      (fields (field (name "MPN") "RMCF0402FT97R6"))
      (libsource (lib "eagle-import") (part "passives_20904581_RESISTOR0402_RES"))
    )
    (comp (ref "R7")
      (value "97.6")
      (footprint "eagle-import:0402_RES")
      (fields (field (name "MPN") "RMCF0402FT97R6"))
      (libsource (lib "eagle-import") (part "passives_20904581_RESISTOR0402_RES"))
    )
    (comp (ref "R8")
      (value "162")
      (footprint "eagle-import:0402_RES")
      (fields (field (name "MPN") "RMCF0402FT162R"))
      (libsource (lib "eagle-import") (part "passives_20904581_RESISTOR0402_RES"))
    )
    (comp (ref "R9")
      (value "162")
      (footprint "eagle-import:0402_RES")
      (fields (field (name "MPN") "RMCF0402FT162R"))
      (libsource (lib "eagle-import") (part "passives_20904581_RESISTOR0402_RES"))
    )
    (comp (ref "R13")
      (value "1k")
      (footprint "eagle-import:0402_RES")
      (libsource (lib "eagle-import") (part "RESISTOR0402_RES"))
    )
    (comp (ref "R14")
      (value "1k")
      (footprint "eagle-import:0402_RES")
      (libsource (lib "eagle-import") (part "RESISTOR0402_RES"))
    )
    (comp (ref "R15")
      (value "2.2k")
      (footprint "eagle-import:0402_RES")
      (fields (field (name "MPN") "RMCF0402JT2K20"))
      (libsource (lib "eagle-import") (part "passives_20904581_RESISTOR0402_RES"))
    )
    (comp (ref "R18")
      (value "10k")
      (footprint "eagle-import:0402_RES")
      (fields (field (name "MPN") "RC0402JR-0710KL"))
      (libsource (lib "eagle-import") (part "RESISTOR0402_RES"))
    )
    (comp (ref "R23")
      (value "10k")
      (footprint "eagle-import:0402_RES")
      (fields (field (name "MPN") "RC0402JR-0710KL"))
      (libsource (lib "eagle-import") (part "RESISTOR0402_RES"))
    )
    (comp (ref "R26")
      (value "261k")
      (footprint "eagle-import:0201_RES")
      (fields (field (name "MPN") "ERJ-1GNF2613C"))
      (libsource (lib "eagle-import") (part "passives_20904581_RESISTOR0201_RES"))
    )
    (comp (ref "R27")
      (value "402k")
      (footprint "eagle-import:0201_RES")
      (fields (field (name "MPN") "ERJ-1GNF4023C"))
      (libsource (lib "eagle-import") (part "passives_20904581_RESISTOR0201_RES"))
    )
    (comp (ref "R28")
      (value "845k")
      (footprint "eagle-import:0201_RES")
      (fields (field (name "MPN") "ERJ-1GNF8453C"))
      (libsource (lib "eagle-import") (part "passives_20904581_RESISTOR0201_RES"))
    )
    (comp (ref "R29")
      (value "845k")
      (footprint "eagle-import:0201_RES")
      (fields (field (name "MPN") "ERJ-1GNF8453C"))
      (libsource (lib "eagle-import") (part "passives_20904581_RESISTOR0201_RES"))
    )
    (comp (ref "R30")
      (value "1.87M")
      (footprint "eagle-import:0402_RES")
      (fields (field (name "MPN") "RMCF0402FT1M87") (field (name "TOLERANCE") "1%"))
      (libsource (lib "eagle-import") (part "RESISTOR0402_RES"))
    )
    (comp (ref "R31")
      (value "5.1M")
      (footprint "eagle-import:0402_RES")
      (fields (field (name "MPN") "RMCF0402FT5M10") (field (name "TOLERANCE") "1%"))
      (libsource (lib "eagle-import") (part "RESISTOR0402_RES"))
    )
    (comp (ref "R33")
      (value "5.1M")
      (footprint "eagle-import:0402_RES")
      (fields (field (name "MPN") "RMCF0402FT5M10"))
      (libsource (lib "eagle-import") (part "RESISTOR0402_RES"))
    )
    (comp (ref "R34")
      (value "5.1M")
      (footprint "eagle-import:0402_RES")
      (fields (field (name "MPN") "RMCF0402FT5M10"))
      (libsource (lib "eagle-import") (part "RESISTOR0402_RES"))
    )
    (comp (ref "RT1")
      (value "10k@25C")
      (footprint "eagle-import:0402_RES")
      (fields (field (name "MPN") "NCU15XH103F60RC"))
      (libsource (lib "eagle-import") (part "THERMISTOR0402"))
    )
    (comp (ref "RX7")
      (value "DNP")
      (footprint "eagle-import:0402_RES")
      (libsource (lib "eagle-import") (part "passives_20904581_RESISTOR0402_RES"))
    )
    (comp (ref "S1")
      (value "450404015514")
      (footprint "eagle-import:450404015514")
      (libsource (lib "eagle-import") (part "450404015514"))
    )
    (comp (ref "U3")
      (value "BQ24040")
      (footprint "eagle-import:DSQ0010A")
      (fields (field (name "MPN") "BQ24040DSQR"))
      (libsource (lib "eagle-import") (part "BQ24040"))
    )
    (comp (ref "U4")
      (value "BQ51013B")
      (footprint "eagle-import:RHL0020A")
      (fields (field (name "MPN") "BQ51013BRHLR"))
      (libsource (lib "eagle-import") (part "BQ51013B"))
    )
    (comp (ref "VR1")
      (value "RT8020RT8020GQW")
      (footprint "eagle-import:SON45P300X300X80-13T160X250N")
      (fields (field (name "MANUFACTURER") "RichTek") (field (name "MPN") "RT8020GQW"))
      (libsource (lib "eagle-import") (part "RT8020RT8020GQW"))
    )
    (comp (ref "XJ1")
      (value "USB4110-GF-A")
      (footprint "eagle-import:GCT_USB4110-GF-A")
      (fields (field (name "MF") "GCT"))
      (libsource (lib "eagle-import") (part "USB4110-GF-A"))
    )
    (comp (ref "XR16")
      (value "5.1k")
      (footprint "eagle-import:0402_RES")
      (fields (field (name "MPN") "RMCF0402FT5K10"))
      (libsource (lib "eagle-import") (part "passives_20904581_RESISTOR0402_RES"))
    )
    (comp (ref "XR17")
      (value "5.1k")
      (footprint "eagle-import:0402_RES")
      (fields (field (name "MPN") "RMCF0402FT5K10"))
      (libsource (lib "eagle-import") (part "passives_20904581_RESISTOR0402_RES"))
    )
    (comp (ref "XR19")
      (value "10k")
      (footprint "eagle-import:0402_RES")
      (fields (field (name "MPN") "RC0402JR-0710KL"))
      (libsource (lib "eagle-import") (part "RESISTOR0402_RES"))
    )
    (comp (ref "A4")
      (value "AMCA72-2R47G-S1F-T")
      (footprint "eagle-import:AMCA72-2R470G-S1F-T")
      (fields (field (name "MPN") "AMCA72-2R470G-S1F-T4"))
      (libsource (lib "eagle-import") (part "AMCA72-2R47G-S1F-T"))
    )
    (comp (ref "C1")
      (value "1.5pF")
      (footprint "eagle-import:CAPC1005X60")
      (description "CAP CER 1.5PF 50V C0G/NP0 0402")
      (fields
        (field (name "MANUFACTURER") "KEMET")
        (field (name "MPN") "C0402C159C5GAC7867")
        (field (name "TEMPCOEFF") "NP0")
        (field (name "TOLERANCE") "+/- 0.25pF")
      )
      (libsource (lib "eagle-import") (part "CCHIP-0402(1005-METRIC)_"))
    )
    (comp (ref "C58")
      (value "2.2uF")
      (footprint "eagle-import:0201_CAP")
      (fields (field (name "MANUFACTURER") "Murata") (field (name "MPN") "GRM033R61A225KE47D"))
      (libsource (lib "eagle-import") (part "passives_20904581_CAPACITOR0201_CAP"))
    )
    (comp (ref "C59")
      (value "2.2uF")
      (footprint "eagle-import:0201_CAP")
      (fields (field (name "MANUFACTURER") "Murata") (field (name "MPN") "GRM033R61A225KE47D"))
      (libsource (lib "eagle-import") (part "passives_20904581_CAPACITOR0201_CAP"))
    )
    (comp (ref "C60")
      (value "2.2uF")
      (footprint "eagle-import:0201_CAP")
      (fields (field (name "MANUFACTURER") "Murata") (field (name "MPN") "GRM033R61A225KE47D"))
      (libsource (lib "eagle-import") (part "passives_20904581_CAPACITOR0201_CAP"))
    )
    (comp (ref "C61")
      (value "2.2uF")
      (footprint "eagle-import:0201_CAP")
      (fields (field (name "MANUFACTURER") "Murata") (field (name "MPN") "GRM033R61A225KE47D"))
      (libsource (lib "eagle-import") (part "passives_20904581_CAPACITOR0201_CAP"))
    )
    (comp (ref "C62")
      (value "1uF")
      (footprint "eagle-import:0201_CAP")
      (fields (field (name "MANUFACTURER") "Murata") (field (name "MPN") "GRM033R61A105ME44D"))
      (libsource (lib "eagle-import") (part "passives_20904581_CAPACITOR0201_CAP"))
    )
    (comp (ref "C63")
      (value "1uF")
      (footprint "eagle-import:0201_CAP")
      (fields (field (name "MANUFACTURER") "Murata") (field (name "MPN") "GRM033R61A105ME44D"))
      (libsource (lib "eagle-import") (part "passives_20904581_CAPACITOR0201_CAP"))
    )
    (comp (ref "C64")
      (value "1uF")
      (footprint "eagle-import:0201_CAP")
      (fields (field (name "MANUFACTURER") "Murata") (field (name "MPN") "GRM033R61A105ME44D"))
      (libsource (lib "eagle-import") (part "passives_20904581_CAPACITOR0201_CAP"))
    )
    (comp (ref "C65")
      (value "1uF")
      (footprint "eagle-import:0201_CAP")
      (fields (field (name "MANUFACTURER") "Murata") (field (name "MPN") "GRM033R61A105ME44D"))
      (libsource (lib "eagle-import") (part "passives_20904581_CAPACITOR0201_CAP"))
    )
    (comp (ref "C66")
      (value "2.2uF")
      (footprint "eagle-import:0201_CAP")
      (fields (field (name "MANUFACTURER") "Murata") (field (name "MPN") "GRM033R61A225KE47D"))
      (libsource (lib "eagle-import") (part "passives_20904581_CAPACITOR0201_CAP"))
    )
    (comp (ref "C67")
      (value "2.2uF")
      (footprint "eagle-import:0201_CAP")
      (fields (field (name "MANUFACTURER") "Murata") (field (name "MPN") "GRM033R61A225KE47D"))
      (libsource (lib "eagle-import") (part "passives_20904581_CAPACITOR0201_CAP"))
    )
    (comp (ref "C69")
      (value "4.7uF")
      (footprint "eagle-import:0402_CAP")
      (fields (field (name "MPN") "CL05A475MP5NRNC"))
      (libsource (lib "eagle-import") (part "CAPACITOR0402_CAP"))
    )
    (comp (ref "C70")
      (value "2.2uF")
      (footprint "eagle-import:0201_CAP")
      (fields (field (name "MANUFACTURER") "Murata") (field (name "MPN") "GRM033R61A225KE47D"))
      (libsource (lib "eagle-import") (part "passives_20904581_CAPACITOR0201_CAP"))
    )
    (comp (ref "C71")
      (value "2.2uF")
      (footprint "eagle-import:0201_CAP")
      (fields (field (name "MANUFACTURER") "Murata") (field (name "MPN") "GRM033R61A225KE47D"))
      (libsource (lib "eagle-import") (part "passives_20904581_CAPACITOR0201_CAP"))
    )
    (comp (ref "C72")
      (value "2.2uF")
      (footprint "eagle-import:0201_CAP")
      (fields (field (name "MANUFACTURER") "Murata") (field (name "MPN") "GRM033R61A225KE47D"))
      (libsource (lib "eagle-import") (part "passives_20904581_CAPACITOR0201_CAP"))
    )
    (comp (ref "C73")
      (value "2.2uF")
      (footprint "eagle-import:0201_CAP")
      (fields (field (name "MANUFACTURER") "Murata") (field (name "MPN") "GRM033R61A225KE47D"))
      (libsource (lib "eagle-import") (part "passives_20904581_CAPACITOR0201_CAP"))
    )
    (comp (ref "C74")
      (value "2.2uF")
      (footprint "eagle-import:0201_CAP")
      (fields (field (name "MANUFACTURER") "Murata") (field (name "MPN") "GRM033R61A225KE47D"))
      (libsource (lib "eagle-import") (part "passives_20904581_CAPACITOR0201_CAP"))
    )
    (comp (ref "C75")
      (value "2.2uF")
      (footprint "eagle-import:0201_CAP")
      (fields (field (name "MANUFACTURER") "Murata") (field (name "MPN") "GRM033R61A225KE47D"))
      (libsource (lib "eagle-import") (part "passives_20904581_CAPACITOR0201_CAP"))
    )
    (comp (ref "C76")
      (value "4700pF")
      (footprint "eagle-import:CAPC1005X60")
      (fields (field (name "MPN") "KGM05AR71E472KH"))
      (libsource (lib "eagle-import") (part "CCHIP-0402(1005-METRIC)_"))
    )
    (comp (ref "C79")
      (value "1uF")
      (footprint "eagle-import:0201_CAP")
      (fields (field (name "MANUFACTURER") "MURATA") (field (name "MPN") "GRM033R61A105ME44D"))
      (libsource (lib "eagle-import") (part "passives_20904581_CAPACITOR0201_CAP"))
    )
    (comp (ref "C80")
      (value "6pF")
      (footprint "eagle-import:CAPC1005X60")
      (fields (field (name "MANUFACTURER") "Murata") (field (name "MPN") "GCM1555C1H6R0BA16D"))
      (libsource (lib "eagle-import") (part "CCHIP-0402(1005-METRIC)_"))
    )
    (comp (ref "C81")
      (value "6pF")
      (footprint "eagle-import:CAPC1005X60")
      (fields (field (name "MANUFACTURER") "Murata") (field (name "MPN") "GCM1555C1H6R0BA16D"))
      (libsource (lib "eagle-import") (part "CCHIP-0402(1005-METRIC)_"))
    )
    (comp (ref "C93")
      (value "1uF")
      (footprint "eagle-import:0201_CAP")
      (fields (field (name "MANUFACTURER") "Murata") (field (name "MPN") "GRM033R61A105ME44D"))
      (libsource (lib "eagle-import") (part "passives_20904581_CAPACITOR0201_CAP"))
    )
    (comp (ref "CX3")
      (value "DNP")
      (footprint "eagle-import:CAPC1005X60")
      (libsource (lib "eagle-import") (part "CCHIP-0402(1005-METRIC)_"))
    )
    (comp (ref "CX4")
      (value "DNP")
      (footprint "eagle-import:CAPC1005X60")
      (libsource (lib "eagle-import") (part "CCHIP-0402(1005-METRIC)_"))
    )
    (comp (ref "CX5")
      (value "DNP")
      (footprint "eagle-import:CAPC1005X60")
      (libsource (lib "eagle-import") (part "CCHIP-0402(1005-METRIC)_"))
    )
    (comp (ref "D3")
      (value "ZENER")
      (footprint "eagle-import:SODFL1608X70")
      (description "DIODE TVS 5.5V STANDOFF 8V BREAKDOWN SC79")
      (fields (field (name "MANUFACTURER") "NXP SEMICONDUCTOR") (field (name "MPN") "PESD5V0X1UB,135"))
      (libsource (lib "eagle-import") (part "ZENERSODFL(1608-METRIC)_"))
    )
    (comp (ref "L5")
      (value "2.2µH")
      (footprint "eagle-import:0805_CAP")
      (fields (field (name "MANUFACTURER") "Murata") (field (name "MPN") "DFE201210U-2R2M=P2"))
      (libsource (lib "eagle-import") (part "INDUCTOR0805"))
    )
    (comp (ref "L6")
      (value "1.0µH")
      (footprint "eagle-import:0603_CAP")
      (fields (field (name "MANUFACTURER") "Murata") (field (name "MPN") "DFE18SAN1R0ME0L"))
      (libsource (lib "eagle-import") (part "INDUCTOR0603"))
    )
    (comp (ref "L7")
      (value "2.0nH")
      (footprint "eagle-import:INDC1006X60N")
      (description "FIXED IND 2.0NH0.1NH SMD")
      (fields
        (field (name "MANUFACTURER") "Central Technologies")
        (field (name "MPN") "CTTF0402F-2N0B")
        (field (name "TOLERANCE") "+/- 0.1 nH")
      )
      (libsource (lib "eagle-import") (part "LCHIP-0402(1006-METRIC)_"))
    )
    (comp (ref "L8")
      (value "2.2nH")
      (footprint "eagle-import:INDC1006X60N")
      (description "FIXED IND 2.2NH0.1NH SMD")
      (fields
        (field (name "MANUFACTURER") "Central Technologies")
        (field (name "MPN") "CTTF0402F-2N2B")
        (field (name "TOLERANCE") "+/- 0.1 nH")
      )
      (libsource (lib "eagle-import") (part "LCHIP-0402(1006-METRIC)_"))
    )
    (comp (ref "RZ9")
      (value "0")
      (footprint "eagle-import:0402_RES")
      (fields (field (name "MPN") "RMCF0402ZT0R00"))
      (libsource (lib "eagle-import") (part "passives_20904581_RESISTOR0402_RES"))
    )
    (comp (ref "TP8")
      (value "VDDBH")
      (footprint "eagle-import:PAD.03X.03")
      (libsource (lib "eagle-import") (part "TEST-POINT"))
    )
    (comp (ref "TP9")
      (value "VDDP")
      (footprint "eagle-import:PAD.03X.03")
      (libsource (lib "eagle-import") (part "TEST-POINT"))
    )
    (comp (ref "TP10")
      (value "VDDF")
      (footprint "eagle-import:PAD.03X.03")
      (libsource (lib "eagle-import") (part "TEST-POINT"))
    )
    (comp (ref "U1")
      (value "APOLLO4_BLUE_PLUS_SOC_KBR")
      (footprint "eagle-import:APOLLO4_BLUE_SOC_BGA")
      (fields (field (name "MANUFACTURER") "Ambiq") (field (name "MPN") "AMA4B2KP-KBR"))
      (libsource (lib "eagle-import") (part "APOLLO4_BLUE_PLUS_SOC_KBR"))
    )
    (comp (ref "X1")
      (value "ABM12W")
      (footprint "eagle-import:ABM12W")
      (fields
        (field (name "C-LOAD") "6pF")
        (field (name "FREQUENCY") "32 MHz")
        (field (name "MANUFACTURER") "Abracon")
        (field (name "MAX-ESR") "80Ω")
        (field (name "MPN") "ABM12W-32.0000MHZ-6-D1X-T3")
      )
      (libsource (lib "eagle-import") (part "ABM12W"))
    )
    (comp (ref "X3")
      (value "TXC-9HT12")
      (footprint "eagle-import:TXC-9HT12")
      (fields
        (field (name "C-LOAD") "7pF")
        (field (name "FREQUENCY") "32.768 kHz")
        (field (name "MANUFACTURER") "TXC Corp")
        (field (name "MPN") "9HT12-32.768KDZY-T")
      )
      (libsource (lib "eagle-import") (part "TXC-9HT12"))
    )
  )
  (nets
    (net (code "1") (name "+1V8") (class "Default")
      (node (ref "C26") (pin "1") (pinfunction "1_1") (pintype "bidirectional"))
      (node (ref "C31") (pin "1") (pinfunction "1_1") (pintype "bidirectional"))
      (node (ref "C35") (pin "1") (pinfunction "1_1") (pintype "bidirectional"))
      (node (ref "C46") (pin "1") (pinfunction "1_1") (pintype "bidirectional"))
      (node (ref "C50") (pin "2") (pinfunction "2_2") (pintype "bidirectional"))
      (node (ref "C62") (pin "P$1") (pinfunction "1_P$1") (pintype "bidirectional"))
      (node (ref "C63") (pin "P$1") (pinfunction "1_P$1") (pintype "bidirectional"))
      (node (ref "C64") (pin "P$1") (pinfunction "1_P$1") (pintype "bidirectional"))
      (node (ref "C65") (pin "P$1") (pinfunction "1_P$1") (pintype "bidirectional"))
      (node (ref "C66") (pin "P$1") (pinfunction "1_P$1") (pintype "bidirectional"))
      (node (ref "C67") (pin "P$1") (pinfunction "1_P$1") (pintype "bidirectional"))
      (node (ref "C75") (pin "P$2") (pinfunction "2_P$2") (pintype "bidirectional"))
      (node (ref "C8") (pin "P$2") (pinfunction "2_P$2") (pintype "bidirectional"))
      (node (ref "J1") (pin "1") (pinfunction "VTREF_1") (pintype "bidirectional"))
      (node (ref "J1") (pin "B1") (pinfunction "VTREF_B1") (pintype "bidirectional"))
      (node (ref "JP1") (pin "2") (pinfunction "2_2") (pintype "passive"))
      (node (ref "JP11") (pin "1") (pinfunction "1_1") (pintype "passive"))
      (node (ref "JP12") (pin "1") (pinfunction "1_1") (pintype "passive"))
      (node (ref "L2") (pin "P$1") (pinfunction "1_P$1") (pintype "bidirectional"))
      (node (ref "R12") (pin "2") (pinfunction "2_2") (pintype "passive"))
      (node (ref "R16") (pin "2") (pinfunction "2_2") (pintype "passive"))
      (node (ref "R20") (pin "2") (pinfunction "2_2") (pintype "passive"))
      (node (ref "R29") (pin "1") (pinfunction "1_1") (pintype "passive"))
      (node (ref "RX2") (pin "2") (pinfunction "2_2") (pintype "passive"))
      (node (ref "RX5") (pin "1") (pinfunction "1_1") (pintype "passive"))
      (node (ref "RX6") (pin "1") (pinfunction "1_1") (pintype "passive"))
      (node (ref "RX8") (pin "2") (pinfunction "2_2") (pintype "passive"))
      (node (ref "RZ12") (pin "2") (pinfunction "2_2") (pintype "passive"))
      (node (ref "S3") (pin "4") (pinfunction "IN_4") (pintype "bidirectional"))
      (node (ref "TP9") (pin "P$1") (pinfunction "TESTPOINT_P$1") (pintype "bidirectional"))
      (node (ref "U1") (pin "B1") (pinfunction "VDDP-IO_PAD_SUP_B1") (pintype "bidirectional"))
      (node (ref "U1") (pin "C4") (pinfunction "VDDA-ANALOG_SUP_C4") (pintype "bidirectional"))
      (node (ref "U1") (pin "E11") (pinfunction "VDDAUDD_E11") (pintype "bidirectional"))
      (node (ref "U1") (pin "G1") (pinfunction "VDDB-BLE_SUPPLY_G1") (pintype "bidirectional"))
      (node (ref "U1") (pin "M10") (pinfunction "VDDH-HV_SUP_M10") (pintype "bidirectional"))
      (node (ref "U1") (pin "M9") (pinfunction "VDDH2-HV_SUP_M9") (pintype "bidirectional"))
      (node (ref "U2") (pin "B13") (pinfunction "VDD1_B13") (pintype "bidirectional"))
      (node (ref "U6") (pin "28") (pinfunction "VDDIO_28") (pintype "input"))
      (node (ref "U8") (pin "8") (pinfunction "VCC_8") (pintype "bidirectional"))
    )
    (net (code "2") (name "+2V5") (class "Default")
      (node (ref "C32") (pin "1") (pinfunction "1_1") (pintype "bidirectional"))
      (node (ref "C34") (pin "1") (pinfunction "1_1") (pintype "bidirectional"))
      (node (ref "C44") (pin "1") (pinfunction "1_1") (pintype "bidirectional"))
      (node (ref "C47") (pin "2") (pinfunction "2_2") (pintype "bidirectional"))
      (node (ref "C49") (pin "1") (pinfunction "1_1") (pintype "bidirectional"))
      (node (ref "C7") (pin "P$1") (pinfunction "1_P$1") (pintype "bidirectional"))
      (node (ref "C77") (pin "P$1") (pinfunction "1_P$1") (pintype "bidirectional"))
      (node (ref "C90") (pin "P$1") (pinfunction "1_P$1") (pintype "bidirectional"))
      (node (ref "D4") (pin "CATHODE") (pinfunction "CATHODE_CATHODE") (pintype "bidirectional"))
      (node (ref "JP10") (pin "1") (pinfunction "1_1") (pintype "passive"))
      (node (ref "L1") (pin "P$2") (pinfunction "2_P$2") (pintype "bidirectional"))
      (node (ref "LS1") (pin "+") (pinfunction "P_+") (pintype "passive"))
      (node (ref "R28") (pin "2") (pinfunction "2_2") (pintype "passive"))
      (node (ref "RX1") (pin "1") (pinfunction "1_1") (pintype "passive"))
      (node (ref "RZ10") (pin "1") (pinfunction "1_1") (pintype "passive"))
      (node (ref "S2") (pin "6") (pinfunction "VDD_6") (pintype "power_in"))
      (node (ref "S3") (pin "1") (pinfunction "IN_1") (pintype "bidirectional"))
      (node (ref "U6") (pin "3") (pinfunction "VDD_3") (pintype "input"))
      (node (ref "VR2") (pin "4") (pinfunction "IN_4") (pintype "bidirectional"))
      (node (ref "VR3") (pin "4") (pinfunction "IN_4") (pintype "bidirectional"))
    )
    (net (code "3") (name "AGND") (class "Default")
      (node (ref "C1") (pin "2") (pinfunction "2_2") (pintype "passive"))
      (node (ref "C93") (pin "P$2") (pinfunction "2_P$2") (pintype "bidirectional"))
      (node (ref "CX5") (pin "2") (pinfunction "2_2") (pintype "passive"))
      (node (ref "U1") (pin "M1") (pinfunction "RFIOM_M1") (pintype "bidirectional"))
      (node (ref "U1") (pin "M3") (pinfunction "RFSUB-RF_SUBSTRATE_GND_M3") (pintype "bidirectional"))
    )
    (net (code "4") (name "ANT1") (class "Default")
      (node (ref "A1") (pin "FEED") (pinfunction "ANTENNA_FEED") (pintype "bidirectional"))
      (node (ref "U7") (pin "2") (pinfunction "LNA_IN_2") (pintype "bidirectional"))
    )
    (net (code "5") (name "AP4_GP06{slash}TT_FLASH_~{HOLD_IO3}") (class "Default")
      (node (ref "U1") (pin "J5") (pinfunction "GPIO6_J5") (pintype "bidirectional"))
      (node (ref "U8") (pin "7") (pinfunction "~{HOLD}/SIO3_7") (pintype "bidirectional"))
    )
    (net (code "6") (name "AP4_GP08{slash}TT_9DOF_H_SCL{slash}SCK{slash}RX") (class "Default")
      (node (ref "RX6") (pin "2") (pinfunction "2_2") (pintype "passive"))
      (node (ref "U1") (pin "H2") (pinfunction "GPIO31_H2") (pintype "bidirectional"))
      (node (ref "U6") (pin "19") (pinfunction "H_SCL/SCK/RX_19") (pintype "bidirectional"))
    )
    (net (code "7") (name "AP4_GP09{slash}TT_9DOF_H_SDA{slash}H_MISO{slash}TX") (class "Default")
      (node (ref "RX5") (pin "2") (pinfunction "2_2") (pintype "passive"))
      (node (ref "U1") (pin "G2") (pinfunction "GPIO32_G2") (pintype "bidirectional"))
      (node (ref "U6") (pin "20") (pinfunction "H_SDA/H_MISO/TX_20") (pintype "bidirectional"))
    )
    (net (code "8") (name "AP4_GP10{slash}TT_9DOF_SA0{slash}H_MOSI") (class "Default")
      (node (ref "U1") (pin "G3") (pinfunction "GPIO33_G3") (pintype "bidirectional"))
      (node (ref "U6") (pin "17") (pinfunction "SA0/H_MOSI_17") (pintype "input"))
    )
    (net (code "9") (name "AP4_GP13{slash}TT_9DOF_~{BOOT}") (class "Default")
      (node (ref "R20") (pin "1") (pinfunction "1_1") (pintype "passive"))
      (node (ref "U1") (pin "D5") (pinfunction "GPIO13_D5") (pintype "bidirectional"))
      (node (ref "U6") (pin "4") (pinfunction "~{BOOT}_4") (pintype "input"))
    )
    (net (code "10") (name "AP4_GP14{slash}TT_~{DW_SPI_CS}") (class "Default")
      (node (ref "U1") (pin "D6") (pinfunction "GPIO14_D6") (pintype "bidirectional"))
      (node (ref "U2") (pin "B5") (pinfunction "~{SPICS}_B5") (pintype "bidirectional"))
    )
    (net (code "11") (name "AP4_GP17{slash}TT_9DOF_H_~{INT}") (class "Default")
      (node (ref "U1") (pin "D4") (pinfunction "GPIO17_D4") (pintype "bidirectional"))
      (node (ref "U6") (pin "14") (pinfunction "H_INTN_14") (pintype "output"))
    )
    (net (code "12") (name "AP4_GP18{slash}TT_BATIN") (class "Default")
      (node (ref "C27") (pin "1") (pinfunction "1_1") (pintype "bidirectional"))
      (node (ref "R30") (pin "2") (pinfunction "2_2") (pintype "passive"))
      (node (ref "R31") (pin "1") (pinfunction "1_1") (pintype "passive"))
      (node (ref "U1") (pin "D3") (pinfunction "GPIO18_D3") (pintype "bidirectional"))
    )
    (net (code "13") (name "AP4_GP24{slash}TT_RFSW_V1") (class "Default")
      (node (ref "CX2") (pin "1") (pinfunction "1_1") (pintype "bidirectional"))
      (node (ref "S2") (pin "4") (pinfunction "V1_4") (pintype "input"))
      (node (ref "U1") (pin "E2") (pinfunction "GPIO24_E2") (pintype "bidirectional"))
    )
    (net (code "14") (name "AP4_GP25{slash}TT_RFSW_V2") (class "Default")
      (node (ref "CX1") (pin "1") (pinfunction "1_1") (pintype "bidirectional"))
      (node (ref "S2") (pin "5") (pinfunction "V2_5") (pintype "input"))
      (node (ref "U1") (pin "K5") (pinfunction "GPIO25_K5") (pintype "bidirectional"))
    )
    (net (code "15") (name "AP4_GP26{slash}TT_DW_WAKEUP") (class "Default")
      (node (ref "U1") (pin "L5") (pinfunction "GPIO26_L5") (pintype "bidirectional"))
      (node (ref "U2") (pin "B9") (pinfunction "WAKEUP_B9") (pintype "bidirectional"))
    )
    (net (code "16") (name "AP4_GP27{slash}TT_DW_IRQ") (class "Default")
      (node (ref "R24") (pin "2") (pinfunction "2_2") (pintype "passive"))
      (node (ref "U1") (pin "M5") (pinfunction "GPIO27_M5") (pintype "bidirectional"))
      (node (ref "U2") (pin "B1") (pinfunction "IRQ/GPIO8_B1") (pintype "bidirectional"))
    )
    (net (code "17") (name "AP4_GP30{slash}TT_FLASH_~{WP}") (class "Default")
      (node (ref "U1") (pin "G4") (pinfunction "GPIO30_G4") (pintype "bidirectional"))
      (node (ref "U8") (pin "3") (pinfunction "~{WP}/SIO2_3") (pintype "bidirectional"))
    )
    (net (code "18") (name "AP4_GP31{slash}TT_DW_SPI_CLK") (class "Default")
      (node (ref "U1") (pin "E8") (pinfunction "GPIO8_E8") (pintype "bidirectional"))
      (node (ref "U2") (pin "A8") (pinfunction "SPICLK_A8") (pintype "bidirectional"))
    )
    (net (code "19") (name "AP4_GP32{slash}TT_DW_SPI_IO0") (class "Default")
      (node (ref "U1") (pin "E7") (pinfunction "GPIO9_E7") (pintype "bidirectional"))
      (node (ref "U2") (pin "B7") (pinfunction "SPICDI(MOSI)_B7") (pintype "bidirectional"))
    )
    (net (code "20") (name "AP4_GP33{slash}TT_DW_SPI_IO1") (class "Default")
      (node (ref "U1") (pin "E6") (pinfunction "GPIO10_E6") (pintype "bidirectional"))
      (node (ref "U2") (pin "A6") (pinfunction "SPICDO(MISO)_A6") (pintype "bidirectional"))
    )
    (net (code "21") (name "AP4_GP47{slash}TT_FLASH_SCK") (class "Default")
      (node (ref "U1") (pin "F1") (pinfunction "GPIO47_F1") (pintype "bidirectional"))
      (node (ref "U8") (pin "6") (pinfunction "SCLK_6") (pintype "input"))
    )
    (net (code "22") (name "AP4_GP48{slash}TT_FLASH_PDI_IO0") (class "Default")
      (node (ref "U1") (pin "E1") (pinfunction "GPIO48_E1") (pintype "bidirectional"))
      (node (ref "U8") (pin "5") (pinfunction "SI/SIO0_5") (pintype "bidirectional"))
    )
    (net (code "23") (name "AP4_GP49{slash}TT_FLASH_PDO_IO1") (class "Default")
      (node (ref "U1") (pin "D1") (pinfunction "GPIO49_D1") (pintype "bidirectional"))
      (node (ref "U8") (pin "2") (pinfunction "SO/SIO1_2") (pintype "bidirectional"))
    )
    (net (code "24") (name "AP4_GP50{slash}TT_~{DW_RESET}") (class "Default")
      (node (ref "U1") (pin "A9") (pinfunction "GPIO50_A9") (pintype "bidirectional"))
      (node (ref "U2") (pin "A10") (pinfunction "~{RST}_A10") (pintype "bidirectional"))
    )
    (net (code "25") (name "AP4_GP51{slash}LED1_GREEN") (class "Default")
      (node (ref "R2") (pin "2") (pinfunction "2_2") (pintype "passive"))
      (node (ref "U1") (pin "B9") (pinfunction "GPIO51_B9") (pintype "bidirectional"))
    )
    (net (code "26") (name "AP4_GP53{slash}LED1_RED") (class "Default")
      (node (ref "R5") (pin "2") (pinfunction "2_2") (pintype "passive"))
      (node (ref "U1") (pin "C9") (pinfunction "GPIO53_C9") (pintype "bidirectional"))
    )
    (net (code "27") (name "AP4_GP55{slash}TT_BUZZER_GATE") (class "Default")
      (node (ref "Q2") (pin "G") (pinfunction "G_G") (pintype "passive"))
      (node (ref "R25") (pin "1") (pinfunction "1_1") (pintype "passive"))
      (node (ref "U1") (pin "D9") (pinfunction "GPIO55_D9") (pintype "bidirectional"))
    )
    (net (code "28") (name "AP4_GP58{slash}TT_~{CHG}") (class "Default")
      (node (ref "U1") (pin "J7") (pinfunction "GPIO58_J7") (pintype "bidirectional"))
      (node (ref "U3") (pin "8") (pinfunction "~{CHG}_8") (pintype "bidirectional"))
      (node (ref "U4") (pin "7") (pinfunction "~{CHG}_7") (pintype "bidirectional"))
    )
    (net (code "29") (name "AP4_GP60{slash}TT_~{PG}") (class "Default")
      (node (ref "U1") (pin "K8") (pinfunction "GPIO60_K8") (pintype "bidirectional"))
      (node (ref "U3") (pin "5") (pinfunction "~{PG}_5") (pintype "bidirectional"))
    )
    (net (code "30") (name "AP4_GP63{slash}TT_9DOF_PS0{slash}WAKE") (class "Default")
      (node (ref "U1") (pin "M6") (pinfunction "GPIO63_M6") (pintype "bidirectional"))
      (node (ref "U6") (pin "6") (pinfunction "PS0/WAKE_6") (pintype "input"))
    )
    (net (code "31") (name "AP4_GP65{slash}TT_9DOF_~{RESET}") (class "Default")
      (node (ref "RX8") (pin "1") (pinfunction "1_1") (pintype "passive"))
      (node (ref "U1") (pin "A7") (pinfunction "GPIO65_A7") (pintype "bidirectional"))
      (node (ref "U6") (pin "11") (pinfunction "~{RESET}_11") (pintype "input"))
    )
    (net (code "32") (name "AP4_GP66{slash}TT_QI_TS_CTRL") (class "Default")
      (node (ref "C30") (pin "1") (pinfunction "1_1") (pintype "bidirectional"))
      (node (ref "RT1") (pin "2") (pinfunction "2_2") (pintype "passive"))
      (node (ref "U1") (pin "A8") (pinfunction "GPIO66_A8") (pintype "bidirectional"))
      (node (ref "U4") (pin "13") (pinfunction "TS/CTRL_13") (pintype "bidirectional"))
    )
    (net (code "33") (name "AP4_GP69{slash}TT_FLASH_~{CS}") (class "Default")
      (node (ref "RX2") (pin "1") (pinfunction "1_1") (pintype "passive"))
      (node (ref "U1") (pin "B8") (pinfunction "GPIO69_B8") (pintype "bidirectional"))
      (node (ref "U8") (pin "1") (pinfunction "~{CS}_1") (pintype "input"))
    )
    (net (code "34") (name "AP4_GP72{slash}TT_9DOF_H_~{CS}") (class "Default")
      (node (ref "U1") (pin "C8") (pinfunction "GPIO72_C8") (pintype "bidirectional"))
      (node (ref "U6") (pin "18") (pinfunction "H_~{CS}_18") (pintype "input"))
    )
    (net (code "35") (name "AP4_GP79{slash}LED2_RED") (class "Default")
      (node (ref "R4") (pin "2") (pinfunction "2_2") (pintype "passive"))
      (node (ref "U1") (pin "M11") (pinfunction "GPIO79_M11") (pintype "bidirectional"))
    )
    (net (code "36") (name "AP4_GP80{slash}SWTRACE0") (class "Default")
      (node (ref "J2") (pin "2") (pinfunction "SWDIO_2") (pintype "bidirectional"))
      (node (ref "J2") (pin "B2") (pinfunction "SWDIO_B2") (pintype "bidirectional"))
      (node (ref "U1") (pin "K10") (pinfunction "GPIO80_K10") (pintype "bidirectional"))
    )
    (net (code "37") (name "AP4_GP81{slash}SWTRACE1") (class "Default")
      (node (ref "J2") (pin "4") (pinfunction "SWDCLK_4") (pintype "bidirectional"))
      (node (ref "J2") (pin "B4") (pinfunction "SWDCLK_B4") (pintype "bidirectional"))
      (node (ref "U1") (pin "L10") (pinfunction "GPIO81_L10") (pintype "bidirectional"))
    )
    (net (code "38") (name "AP4_GP82{slash}SWTRACE2") (class "Default")
      (node (ref "J2") (pin "6") (pinfunction "SWO_6") (pintype "bidirectional"))
      (node (ref "J2") (pin "B6") (pinfunction "SWO_B6") (pintype "bidirectional"))
      (node (ref "U1") (pin "L9") (pinfunction "GPIO82_L9") (pintype "bidirectional"))
    )
    (net (code "39") (name "AP4_GP83{slash}SWTRACE3") (class "Default")
      (node (ref "J2") (pin "3") (pinfunction "~{RESET}_3") (pintype "bidirectional"))
      (node (ref "J2") (pin "B3") (pinfunction "~{RESET}_B3") (pintype "bidirectional"))
      (node (ref "U1") (pin "K9") (pinfunction "GPIO83_K9") (pintype "bidirectional"))
    )
    (net (code "40") (name "AP4_GP88{slash}LED2_YLW") (class "Default")
      (node (ref "R3") (pin "2") (pinfunction "2_2") (pintype "passive"))
      (node (ref "U1") (pin "F9") (pinfunction "GPIO88_F9") (pintype "bidirectional"))
    )
    (net (code "41") (name "AP4_SWDCLK") (class "Default")
      (node (ref "J1") (pin "4") (pinfunction "SWDCLK_4") (pintype "bidirectional"))
      (node (ref "J1") (pin "B4") (pinfunction "SWDCLK_B4") (pintype "bidirectional"))
      (node (ref "U1") (pin "K3") (pinfunction "GPIO20_K3") (pintype "bidirectional"))
    )
    (net (code "42") (name "AP4_SWDIO") (class "Default")
      (node (ref "J1") (pin "2") (pinfunction "SWDIO_2") (pintype "bidirectional"))
      (node (ref "J1") (pin "B2") (pinfunction "SWDIO_B2") (pintype "bidirectional"))
      (node (ref "U1") (pin "J3") (pinfunction "GPIO21_J3") (pintype "bidirectional"))
    )
    (net (code "43") (name "AP4_SWO") (class "Default")
      (node (ref "J1") (pin "6") (pinfunction "SWO_6") (pintype "bidirectional"))
      (node (ref "J1") (pin "B6") (pinfunction "SWO_B6") (pintype "bidirectional"))
      (node (ref "U1") (pin "L4") (pinfunction "GPIO3_L4") (pintype "bidirectional"))
    )
    (net (code "44") (name "AP4_SWTRACECLK") (class "Default")
      (node (ref "J2") (pin "1") (pinfunction "VTREF_1") (pintype "bidirectional"))
      (node (ref "J2") (pin "B1") (pinfunction "VTREF_B1") (pintype "bidirectional"))
      (node (ref "U1") (pin "F12") (pinfunction "GPIO38_F12") (pintype "bidirectional"))
    )
    (net (code "45") (name "AP4_USB0_N") (class "Default")
      (node (ref "U1") (pin "M8") (pinfunction "USB0PN_M8") (pintype "bidirectional"))
    )
    (net (code "46") (name "AP4_USB0_P") (class "Default")
      (node (ref "U1") (pin "M7") (pinfunction "USB0PP_M7") (pintype "bidirectional"))
    )
    (net (code "47") (name "AP4_VDDBH") (class "Default")
      (node (ref "C69") (pin "1") (pinfunction "1_1") (pintype "bidirectional"))
      (node (ref "L6") (pin "2") (pinfunction "2_2") (pintype "bidirectional"))
      (node (ref "RZ9") (pin "1") (pinfunction "1_1") (pintype "passive"))
      (node (ref "TP8") (pin "P$1") (pinfunction "TESTPOINT_P$1") (pintype "bidirectional"))
      (node (ref "U1") (pin "G12") (pinfunction "VDDBH--BLE_BUCK_VOUT_G12") (pintype "bidirectional"))
    )
    (net (code "48") (name "AP4_VDDBH_RF") (class "Default")
      (node (ref "C93") (pin "P$1") (pinfunction "1_P$1") (pintype "bidirectional"))
      (node (ref "RZ9") (pin "2") (pinfunction "2_2") (pintype "passive"))
      (node (ref "U1") (pin "J1") (pinfunction "VDDBH_RF--BLE_BUCK_RF_VOUT_J1") (pintype "bidirectional"))
    )
    (net (code "49") (name "AP4_VDDF") (class "Default")
      (node (ref "C61") (pin "P$1") (pinfunction "1_P$1") (pintype "bidirectional"))
      (node (ref "C75") (pin "P$1") (pinfunction "1_P$1") (pintype "bidirectional"))
      (node (ref "TP10") (pin "P$1") (pinfunction "TESTPOINT_P$1") (pintype "bidirectional"))
      (node (ref "U1") (pin "C2") (pinfunction "VDDF-MEM_C2") (pintype "bidirectional"))
    )
    (net (code "50") (name "AP4_VDDMIPI_1P8") (class "Default")
      (node (ref "C70") (pin "P$1") (pinfunction "1_P$1") (pintype "bidirectional"))
      (node (ref "RZ8") (pin "1") (pinfunction "1_1") (pintype "passive"))
      (node (ref "U1") (pin "H10") (pinfunction "VDD18-MIPI_H10") (pintype "bidirectional"))
    )
    (net (code "51") (name "AP4_VDDUSB_0P9") (class "Default")
      (node (ref "C73") (pin "P$1") (pinfunction "1_P$1") (pintype "bidirectional"))
      (node (ref "RZ6") (pin "1") (pinfunction "1_1") (pintype "passive"))
      (node (ref "U1") (pin "L7") (pinfunction "VDDUSB0P9_L7") (pintype "bidirectional"))
    )
    (net (code "52") (name "AP4_VDDUSB_3P3") (class "Default")
      (node (ref "C74") (pin "P$1") (pinfunction "1_P$1") (pintype "bidirectional"))
      (node (ref "RZ7") (pin "1") (pinfunction "1_1") (pintype "passive"))
      (node (ref "U1") (pin "K7") (pinfunction "VDDUSB33_K7") (pintype "bidirectional"))
    )
    (net (code "53") (name "AP4_~{RESET}") (class "Default")
      (node (ref "C76") (pin "1") (pinfunction "1_1") (pintype "passive"))
      (node (ref "D3") (pin "1") (pinfunction "C_1") (pintype "passive"))
      (node (ref "J1") (pin "3") (pinfunction "~{RESET}_3") (pintype "bidirectional"))
      (node (ref "J1") (pin "B3") (pinfunction "~{RESET}_B3") (pintype "bidirectional"))
      (node (ref "U1") (pin "A6") (pinfunction "~{RST}_A6") (pintype "input"))
    )
    (net (code "54") (name "BATT_THERM") (class "Default")
      (node (ref "J4") (pin "2") (pinfunction "2_2") (pintype "bidirectional"))
      (node (ref "J4") (pin "2SUPP") (pinfunction "2_2SUPP") (pintype "bidirectional"))
      (node (ref "JP2") (pin "3") (pinfunction "3_3") (pintype "passive"))
    )
    (net (code "55") (name "BATT_TS") (class "Default")
      (node (ref "JP2") (pin "2") (pinfunction "2_2") (pintype "passive"))
      (node (ref "U3") (pin "9") (pinfunction "TS_9") (pintype "bidirectional"))
    )
    (net (code "56") (name "BNO_ENV_SCL") (class "Default")
      (node (ref "R12") (pin "1") (pinfunction "1_1") (pintype "passive"))
      (node (ref "U6") (pin "15") (pinfunction "ENV_SCL_15") (pintype "bidirectional"))
    )
    (net (code "57") (name "BNO_ENV_SDA") (class "Default")
      (node (ref "R16") (pin "1") (pinfunction "1_1") (pintype "passive"))
      (node (ref "U6") (pin "16") (pinfunction "ENV_SDA_16") (pintype "bidirectional"))
    )
    (net (code "58") (name "D+") (class "Default")
      (node (ref "XJ1") (pin "A6") (pinfunction "DP1_A6") (pintype "bidirectional"))
      (node (ref "XJ1") (pin "B6") (pinfunction "DP2_B6") (pintype "bidirectional"))
    )
    (net (code "59") (name "D-") (class "Default")
      (node (ref "XJ1") (pin "A7") (pinfunction "DN1_A7") (pintype "bidirectional"))
      (node (ref "XJ1") (pin "B7") (pinfunction "DN2_B7") (pintype "bidirectional"))
    )
    (net (code "60") (name "DW_EXTON") (class "Default")
      (node (ref "JP12") (pin "2") (pinfunction "2_2") (pintype "passive"))
      (node (ref "RX1") (pin "2") (pinfunction "2_2") (pintype "passive"))
      (node (ref "S3") (pin "2") (pinfunction "CTL_2") (pintype "bidirectional"))
      (node (ref "S3") (pin "3") (pinfunction "CTL_3") (pintype "bidirectional"))
      (node (ref "VR3") (pin "3") (pinfunction "EN_3") (pintype "input"))
    )
    (net (code "61") (name "DW_EXTON_RAW") (class "Default")
      (node (ref "JP12") (pin "3") (pinfunction "3_3") (pintype "passive"))
      (node (ref "U2") (pin "A12") (pinfunction "EXTON_A12") (pintype "bidirectional"))
    )
    (net (code "62") (name "DW_GPIO6{slash}EXTRXE") (class "Default")
      (node (ref "JP3") (pin "3") (pinfunction "3_3") (pintype "passive"))
      (node (ref "TP6") (pin "P$1") (pinfunction "TESTPOINT_P$1") (pintype "bidirectional"))
      (node (ref "U2") (pin "C4") (pinfunction "GPIO6/EXTRXE/SPIPHA_C4") (pintype "bidirectional"))
    )
    (net (code "63") (name "DW_SYNC") (class "Default")
      (node (ref "TP7") (pin "P$1") (pinfunction "TESTPOINT_P$1") (pintype "bidirectional"))
      (node (ref "U2") (pin "G2") (pinfunction "GPIO7/SYNC_G2") (pintype "bidirectional"))
    )
    (net (code "64") (name "DW_VDD2_SUP") (class "Default")
      (node (ref "C13") (pin "P$1") (pinfunction "P$1_P$1") (pintype "bidirectional"))
      (node (ref "C24") (pin "P$1") (pinfunction "P$1_P$1") (pintype "bidirectional"))
      (node (ref "C55") (pin "P$1") (pinfunction "P$1_P$1") (pintype "bidirectional"))
      (node (ref "FB1") (pin "P$1") (pinfunction "P$1_P$1") (pintype "bidirectional"))
      (node (ref "RZ1") (pin "2") (pinfunction "2_2") (pintype "passive"))
      (node (ref "U2") (pin "B15") (pinfunction "VDD2B_B15") (pintype "bidirectional"))
    )
    (net (code "65") (name "DW_VDD3_SUP") (class "Default")
      (node (ref "C14") (pin "P$2") (pinfunction "P$2_P$2") (pintype "bidirectional"))
      (node (ref "C22") (pin "P$2") (pinfunction "P$2_P$2") (pintype "bidirectional"))
      (node (ref "C54") (pin "P$2") (pinfunction "P$2_P$2") (pintype "bidirectional"))
      (node (ref "RZ2") (pin "2") (pinfunction "2_2") (pintype "passive"))
      (node (ref "U2") (pin "D15") (pinfunction "VDD3_D15") (pintype "bidirectional"))
    )
    (net (code "66") (name "GND") (class "Default")
      (node (ref "C11") (pin "P$2") (pinfunction "P$2_P$2") (pintype "bidirectional"))
      (node (ref "C12") (pin "P$2") (pinfunction "P$2_P$2") (pintype "bidirectional"))
      (node (ref "C13") (pin "P$2") (pinfunction "P$2_P$2") (pintype "bidirectional"))
      (node (ref "C14") (pin "P$1") (pinfunction "P$1_P$1") (pintype "bidirectional"))
      (node (ref "C22") (pin "P$1") (pinfunction "P$1_P$1") (pintype "bidirectional"))
      (node (ref "C23") (pin "2") (pinfunction "2_2") (pintype "bidirectional"))
      (node (ref "C24") (pin "P$2") (pinfunction "P$2_P$2") (pintype "bidirectional"))
      (node (ref "C25") (pin "2") (pinfunction "2_2") (pintype "bidirectional"))
      (node (ref "C26") (pin "2") (pinfunction "2_2") (pintype "bidirectional"))
      (node (ref "C27") (pin "2") (pinfunction "2_2") (pintype "bidirectional"))
      (node (ref "C28") (pin "2") (pinfunction "2_2") (pintype "bidirectional"))
      (node (ref "C29") (pin "2") (pinfunction "2_2") (pintype "bidirectional"))
      (node (ref "C3") (pin "P$2") (pinfunction "P$2_P$2") (pintype "bidirectional"))
      (node (ref "C30") (pin "2") (pinfunction "2_2") (pintype "bidirectional"))
      (node (ref "C31") (pin "2") (pinfunction "2_2") (pintype "bidirectional"))
      (node (ref "C32") (pin "2") (pinfunction "2_2") (pintype "bidirectional"))
      (node (ref "C33") (pin "2") (pinfunction "2_2") (pintype "bidirectional"))
      (node (ref "C34") (pin "2") (pinfunction "2_2") (pintype "bidirectional"))
      (node (ref "C35") (pin "2") (pinfunction "2_2") (pintype "bidirectional"))
      (node (ref "C36") (pin "2") (pinfunction "2_2") (pintype "bidirectional"))
      (node (ref "C37") (pin "P$1") (pinfunction "P$1_P$1") (pintype "bidirectional"))
      (node (ref "C4") (pin "P$2") (pinfunction "P$2_P$2") (pintype "bidirectional"))
      (node (ref "C40") (pin "1") (pinfunction "1_1") (pintype "bidirectional"))
      (node (ref "C41") (pin "2") (pinfunction "2_2") (pintype "bidirectional"))
      (node (ref "C42") (pin "2") (pinfunction "2_2") (pintype "bidirectional"))
      (node (ref "C43") (pin "P$2") (pinfunction "P$2_P$2") (pintype "bidirectional"))
      (node (ref "C44") (pin "2") (pinfunction "2_2") (pintype "bidirectional"))
      (node (ref "C45") (pin "1") (pinfunction "1_1") (pintype "bidirectional"))
      (node (ref "C46") (pin "2") (pinfunction "2_2") (pintype "bidirectional"))
      (node (ref "C47") (pin "1") (pinfunction "1_1") (pintype "bidirectional"))
      (node (ref "C48") (pin "2") (pinfunction "2_2") (pintype "bidirectional"))
      (node (ref "C49") (pin "2") (pinfunction "2_2") (pintype "bidirectional"))
      (node (ref "C5") (pin "P$1") (pinfunction "1_P$1") (pintype "bidirectional"))
      (node (ref "C50") (pin "1") (pinfunction "1_1") (pintype "bidirectional"))
      (node (ref "C53") (pin "2") (pinfunction "2_2") (pintype "bidirectional"))
      (node (ref "C54") (pin "P$1") (pinfunction "P$1_P$1") (pintype "bidirectional"))
      (node (ref "C55") (pin "P$2") (pinfunction "P$2_P$2") (pintype "bidirectional"))
      (node (ref "C56") (pin "2") (pinfunction "2_2") (pintype "bidirectional"))
      (node (ref "C57") (pin "2") (pinfunction "2_2") (pintype "bidirectional"))
      (node (ref "C58") (pin "P$2") (pinfunction "2_P$2") (pintype "bidirectional"))
      (node (ref "C59") (pin "P$2") (pinfunction "2_P$2") (pintype "bidirectional"))
      (node (ref "C6") (pin "P$1") (pinfunction "1_P$1") (pintype "bidirectional"))
      (node (ref "C60") (pin "P$2") (pinfunction "2_P$2") (pintype "bidirectional"))
      (node (ref "C61") (pin "P$2") (pinfunction "2_P$2") (pintype "bidirectional"))
      (node (ref "C62") (pin "P$2") (pinfunction "2_P$2") (pintype "bidirectional"))
      (node (ref "C63") (pin "P$2") (pinfunction "2_P$2") (pintype "bidirectional"))
      (node (ref "C64") (pin "P$2") (pinfunction "2_P$2") (pintype "bidirectional"))
      (node (ref "C65") (pin "P$2") (pinfunction "2_P$2") (pintype "bidirectional"))
      (node (ref "C66") (pin "P$2") (pinfunction "2_P$2") (pintype "bidirectional"))
      (node (ref "C67") (pin "P$2") (pinfunction "2_P$2") (pintype "bidirectional"))
      (node (ref "C69") (pin "2") (pinfunction "2_2") (pintype "bidirectional"))
      (node (ref "C70") (pin "P$2") (pinfunction "2_P$2") (pintype "bidirectional"))
      (node (ref "C71") (pin "P$1") (pinfunction "1_P$1") (pintype "bidirectional"))
      (node (ref "C72") (pin "P$2") (pinfunction "2_P$2") (pintype "bidirectional"))
      (node (ref "C73") (pin "P$2") (pinfunction "2_P$2") (pintype "bidirectional"))
      (node (ref "C74") (pin "P$2") (pinfunction "2_P$2") (pintype "bidirectional"))
      (node (ref "C76") (pin "2") (pinfunction "2_2") (pintype "passive"))
      (node (ref "C77") (pin "P$2") (pinfunction "2_P$2") (pintype "bidirectional"))
      (node (ref "C78") (pin "P$2") (pinfunction "2_P$2") (pintype "bidirectional"))
      (node (ref "C79") (pin "P$1") (pinfunction "1_P$1") (pintype "bidirectional"))
      (node (ref "C80") (pin "2") (pinfunction "2_2") (pintype "passive"))
      (node (ref "C81") (pin "2") (pinfunction "2_2") (pintype "passive"))
      (node (ref "C90") (pin "P$2") (pinfunction "2_P$2") (pintype "bidirectional"))
      (node (ref "C91") (pin "P$2") (pinfunction "2_P$2") (pintype "bidirectional"))
      (node (ref "CX1") (pin "2") (pinfunction "2_2") (pintype "bidirectional"))
      (node (ref "CX2") (pin "2") (pinfunction "2_2") (pintype "bidirectional"))
      (node (ref "CX3") (pin "2") (pinfunction "2_2") (pintype "passive"))
      (node (ref "CX4") (pin "2") (pinfunction "2_2") (pintype "passive"))
      (node (ref "D3") (pin "2") (pinfunction "A_2") (pintype "passive"))
      (node (ref "J1") (pin "5") (pinfunction "GND_5") (pintype "bidirectional"))
      (node (ref "J1") (pin "B5") (pinfunction "GND_B5") (pintype "bidirectional"))
      (node (ref "J2") (pin "5") (pinfunction "GND_5") (pintype "bidirectional"))
      (node (ref "J2") (pin "B5") (pinfunction "GND_B5") (pintype "bidirectional"))
      (node (ref "J4") (pin "1") (pinfunction "1_1") (pintype "bidirectional"))
      (node (ref "J4") (pin "1SUPP") (pinfunction "1_1SUPP") (pintype "bidirectional"))
      (node (ref "JP3") (pin "1") (pinfunction "1_1") (pintype "passive"))
      (node (ref "JP9") (pin "2") (pinfunction "2_2") (pintype "passive"))
      (node (ref "Q2") (pin "S") (pinfunction "S_S") (pintype "passive"))
      (node (ref "R1") (pin "2") (pinfunction "2_2") (pintype "passive"))
      (node (ref "R14") (pin "1") (pinfunction "1_1") (pintype "passive"))
      (node (ref "R15") (pin "1") (pinfunction "1_1") (pintype "passive"))
      (node (ref "R24") (pin "1") (pinfunction "1_1") (pintype "passive"))
      (node (ref "R25") (pin "2") (pinfunction "2_2") (pintype "passive"))
      (node (ref "R26") (pin "1") (pinfunction "1_1") (pintype "passive"))
      (node (ref "R27") (pin "1") (pinfunction "1_1") (pintype "passive"))
      (node (ref "R30") (pin "1") (pinfunction "1_1") (pintype "passive"))
      (node (ref "R6") (pin "2") (pinfunction "2_2") (pintype "passive"))
      (node (ref "RX7") (pin "1") (pinfunction "1_1") (pintype "passive"))
      (node (ref "RX9") (pin "1") (pinfunction "1_1") (pintype "passive"))
      (node (ref "RZ6") (pin "2") (pinfunction "2_2") (pintype "passive"))
      (node (ref "RZ7") (pin "2") (pinfunction "2_2") (pintype "passive"))
      (node (ref "RZ8") (pin "2") (pinfunction "2_2") (pintype "passive"))
      (node (ref "S2") (pin "10") (pinfunction "GND_10") (pintype "bidirectional"))
      (node (ref "S2") (pin "12") (pinfunction "GND_12") (pintype "bidirectional"))
      (node (ref "S2") (pin "2") (pinfunction "GND_2") (pintype "bidirectional"))
      (node (ref "S2") (pin "7") (pinfunction "GND_7") (pintype "bidirectional"))
      (node (ref "S2") (pin "8") (pinfunction "GND_8") (pintype "bidirectional"))
      (node (ref "S2") (pin "PAD") (pinfunction "GND_PAD") (pintype "bidirectional"))
      (node (ref "S3") (pin "6") (pinfunction "GND_6") (pintype "bidirectional"))
      (node (ref "S3") (pin "7") (pinfunction "GND_7") (pintype "bidirectional"))
      (node (ref "S3") (pin "PAD") (pinfunction "GND_PAD") (pintype "bidirectional"))
      (node (ref "S4") (pin "G1") (pinfunction "GND_G1") (pintype "bidirectional"))
      (node (ref "S4") (pin "G2") (pinfunction "GND_G2") (pintype "bidirectional"))
      (node (ref "U1") (pin "B12") (pinfunction "VSSAUDA_B12") (pintype "bidirectional"))
      (node (ref "U1") (pin "B2") (pinfunction "VSSP-BUCK_REGS_GND_B2") (pintype "bidirectional"))
      (node (ref "U1") (pin "B5") (pinfunction "VSSA-ANALOG_GND_B5") (pintype "bidirectional"))
      (node (ref "U1") (pin "D2") (pinfunction "VSS-DGND_FOR_VDDF_AND_PADS_D2") (pintype "bidirectional"))
      (node (ref "U1") (pin "E12") (pinfunction "VSSAUDD_E12") (pintype "bidirectional"))
      (node (ref "U1") (pin "H1") (pinfunction "VSSB-BLE_UNREG_GND_H1") (pintype "bidirectional"))
      (node (ref "U1") (pin "J10") (pinfunction "VSS18-MIPI_J10") (pintype "bidirectional"))
      (node (ref "U1") (pin "L1") (pinfunction "VSSVCO-BLECORE_GND_FOR_VCO_L1") (pintype "bidirectional"))
      (node (ref "U1") (pin "L2") (pinfunction "VSSS-HVSIMOBUCK_GND_L2") (pintype "bidirectional"))
      (node (ref "U1") (pin "L8") (pinfunction "VSSAUSB_L8") (pintype "bidirectional"))
      (node (ref "U2") (pin "A14") (pinfunction "VSS1_A14") (pintype "bidirectional"))
      (node (ref "U2") (pin "A2") (pinfunction "VSS_A2") (pintype "bidirectional"))
      (node (ref "U2") (pin "B11") (pinfunction "VSS1_B11") (pintype "bidirectional"))
      (node (ref "U2") (pin "B3") (pinfunction "VSS_B3") (pintype "bidirectional"))
      (node (ref "U2") (pin "C10") (pinfunction "VSS1_C10") (pintype "bidirectional"))
      (node (ref "U2") (pin "C12") (pinfunction "VSS3_C12") (pintype "bidirectional"))
      (node (ref "U2") (pin "C6") (pinfunction "VSS_C6") (pintype "bidirectional"))
      (node (ref "U2") (pin "C8") (pinfunction "VSS1_C8") (pintype "bidirectional"))
      (node (ref "U2") (pin "D11") (pinfunction "VSS2_D11") (pintype "bidirectional"))
      (node (ref "U2") (pin "D13") (pinfunction "VSS3_D13") (pintype "bidirectional"))
      (node (ref "U2") (pin "D5") (pinfunction "VSS_D5") (pintype "bidirectional"))
      (node (ref "U2") (pin "D7") (pinfunction "VSS_D7") (pintype "bidirectional"))
      (node (ref "U2") (pin "D9") (pinfunction "VSS1_D9") (pintype "bidirectional"))
      (node (ref "U2") (pin "E10") (pinfunction "GND-RF_E10") (pintype "bidirectional"))
      (node (ref "U2") (pin "E12") (pinfunction "GND-RF_E12") (pintype "bidirectional"))
      (node (ref "U2") (pin "E14") (pinfunction "VSS2_E14") (pintype "bidirectional"))
      (node (ref "U2") (pin "E6") (pinfunction "GND-RF_E6") (pintype "bidirectional"))
      (node (ref "U2") (pin "F7") (pinfunction "GND-RF_F7") (pintype "bidirectional"))
      (node (ref "U2") (pin "F9") (pinfunction "GND-RF_F9") (pintype "bidirectional"))
      (node (ref "U2") (pin "G10") (pinfunction "GND-RF_G10") (pintype "bidirectional"))
      (node (ref "U2") (pin "G6") (pinfunction "GND-RF_G6") (pintype "bidirectional"))
      (node (ref "U2") (pin "H1") (pinfunction "GND-RF_H1") (pintype "bidirectional"))
      (node (ref "U2") (pin "H13") (pinfunction "GND-RF_H13") (pintype "bidirectional"))
      (node (ref "U2") (pin "H3") (pinfunction "GND-RF_H3") (pintype "bidirectional"))
      (node (ref "U2") (pin "H7") (pinfunction "GND-RF_H7") (pintype "bidirectional"))
      (node (ref "U2") (pin "H9") (pinfunction "GND-RF_H9") (pintype "bidirectional"))
      (node (ref "U3") (pin "3") (pinfunction "VSS_3") (pintype "bidirectional"))
      (node (ref "U3") (pin "7") (pinfunction "ISET2_7") (pintype "bidirectional"))
      (node (ref "U3") (pin "PAD") (pinfunction "VSS_PAD") (pintype "bidirectional"))
      (node (ref "U4") (pin "1") (pinfunction "PGND_1") (pintype "bidirectional"))
      (node (ref "U4") (pin "10") (pinfunction "EN1_10") (pintype "bidirectional"))
      (node (ref "U4") (pin "11") (pinfunction "EN2_11") (pintype "bidirectional"))
      (node (ref "U4") (pin "20") (pinfunction "PGND_20") (pintype "bidirectional"))
      (node (ref "U4") (pin "PAD") (pinfunction "PGND_PAD") (pintype "bidirectional"))
      (node (ref "U6") (pin "10") (pinfunction "CLKSEL0_10") (pintype "output"))
      (node (ref "U6") (pin "2") (pinfunction "GND_2") (pintype "bidirectional"))
      (node (ref "U6") (pin "25") (pinfunction "GNDIO_25") (pintype "bidirectional"))
      (node (ref "U7") (pin "3") (pinfunction "GND_3") (pintype "bidirectional"))
      (node (ref "U7") (pin "4") (pinfunction "GND_4") (pintype "bidirectional"))
      (node (ref "U7") (pin "5") (pinfunction "GND_5") (pintype "bidirectional"))
      (node (ref "U7") (pin "7") (pinfunction "GND_7") (pintype "bidirectional"))
      (node (ref "U7") (pin "9") (pinfunction "GND_9") (pintype "bidirectional"))
      (node (ref "U8") (pin "4") (pinfunction "GND_4") (pintype "bidirectional"))
      (node (ref "VR1") (pin "13") (pinfunction "GND2_13") (pintype "bidirectional"))
      (node (ref "VR1") (pin "3") (pinfunction "GND2_3") (pintype "bidirectional"))
      (node (ref "VR1") (pin "9") (pinfunction "GND1_9") (pintype "bidirectional"))
      (node (ref "VR2") (pin "2") (pinfunction "GND_2") (pintype "bidirectional"))
      (node (ref "VR2") (pin "PAD") (pinfunction "GND_PAD") (pintype "bidirectional"))
      (node (ref "VR3") (pin "2") (pinfunction "GND_2") (pintype "bidirectional"))
      (node (ref "VR3") (pin "PAD") (pinfunction "GND_PAD") (pintype "bidirectional"))
      (node (ref "X1") (pin "2") (pinfunction "GND_2") (pintype "bidirectional"))
      (node (ref "X1") (pin "4") (pinfunction "GND_4") (pintype "bidirectional"))
      (node (ref "X4") (pin "2") (pinfunction "GND_2") (pintype "bidirectional"))
      (node (ref "X4") (pin "4") (pinfunction "GND_4") (pintype "bidirectional"))
      (node (ref "XJ1") (pin "A1/B12") (pinfunction "GND_A1/B12") (pintype "power_in"))
      (node (ref "XJ1") (pin "B1/A12") (pinfunction "GND_B1/A12") (pintype "power_in"))
      (node (ref "XJ1") (pin "S1") (pinfunction "GND_S1") (pintype "power_in"))
      (node (ref "XJ1") (pin "S2") (pinfunction "GND_S2") (pintype "power_in"))
      (node (ref "XJ1") (pin "S3") (pinfunction "GND_S3") (pintype "power_in"))
      (node (ref "XJ1") (pin "S4") (pinfunction "GND_S4") (pintype "power_in"))
      (node (ref "XR16") (pin "2") (pinfunction "2_2") (pintype "passive"))
      (node (ref "XR17") (pin "2") (pinfunction "2_2") (pintype "passive"))
      (node (ref "XR19") (pin "1") (pinfunction "1_1") (pintype "passive"))
    )
    (net (code "67") (name "Net-(A4-ANTENNA)") (class "Default")
      (node (ref "A4") (pin "S1") (pinfunction "ANTENNA_S1") (pintype "bidirectional"))
      (node (ref "L8") (pin "2") (pinfunction "2_2") (pintype "passive"))
    )
    (net (code "68") (name "Net-(C1-Pad1)") (class "Default")
      (node (ref "C1") (pin "1") (pinfunction "1_1") (pintype "passive"))
      (node (ref "L7") (pin "2") (pinfunction "2_2") (pintype "passive"))
      (node (ref "L8") (pin "1") (pinfunction "1_1") (pintype "passive"))
    )
    (net (code "69") (name "Net-(C2-1)") (class "Default")
      (node (ref "C2") (pin "P$1") (pinfunction "1_P$1") (pintype "bidirectional"))
      (node (ref "U2") (pin "H11") (pinfunction "RF1_H11") (pintype "bidirectional"))
    )
    (net (code "70") (name "Net-(C2-2)") (class "Default")
      (node (ref "C2") (pin "P$2") (pinfunction "2_P$2") (pintype "bidirectional"))
      (node (ref "S2") (pin "11") (pinfunction "RFC_11") (pintype "bidirectional"))
    )
    (net (code "71") (name "Net-(C5-2)") (class "Default")
      (node (ref "C5") (pin "P$2") (pinfunction "2_P$2") (pintype "bidirectional"))
      (node (ref "U6") (pin "27") (pinfunction "XIN32_27") (pintype "bidirectional"))
      (node (ref "X2") (pin "2") (pinfunction "2_2") (pintype "bidirectional"))
    )
    (net (code "72") (name "Net-(C6-2)") (class "Default")
      (node (ref "C6") (pin "P$2") (pinfunction "2_P$2") (pintype "bidirectional"))
      (node (ref "U6") (pin "26") (pinfunction "XOUT32/CLKSEL1_26") (pintype "bidirectional"))
      (node (ref "X2") (pin "1") (pinfunction "1_1") (pintype "bidirectional"))
    )
    (net (code "73") (name "Net-(C7-2)") (class "Default")
      (node (ref "C7") (pin "P$2") (pinfunction "2_P$2") (pintype "bidirectional"))
      (node (ref "R26") (pin "2") (pinfunction "2_2") (pintype "passive"))
      (node (ref "R28") (pin "1") (pinfunction "1_1") (pintype "passive"))
      (node (ref "VR1") (pin "10") (pinfunction "FB2_10") (pintype "bidirectional"))
    )
    (net (code "74") (name "Net-(C8-1)") (class "Default")
      (node (ref "C8") (pin "P$1") (pinfunction "1_P$1") (pintype "bidirectional"))
      (node (ref "R27") (pin "2") (pinfunction "2_2") (pintype "passive"))
      (node (ref "R29") (pin "2") (pinfunction "2_2") (pintype "passive"))
      (node (ref "VR1") (pin "4") (pinfunction "FB1_4") (pintype "bidirectional"))
    )
    (net (code "75") (name "Net-(C58-1)") (class "Default")
      (node (ref "C58") (pin "P$1") (pinfunction "1_P$1") (pintype "bidirectional"))
      (node (ref "U1") (pin "C1") (pinfunction "VDDS-SRAM_HV_SUP_C1") (pintype "bidirectional"))
    )
    (net (code "76") (name "Net-(C59-1)") (class "Default")
      (node (ref "C59") (pin "P$1") (pinfunction "1_P$1") (pintype "bidirectional"))
      (node (ref "U1") (pin "A3") (pinfunction "VDDC-CORE_A3") (pintype "bidirectional"))
    )
    (net (code "77") (name "Net-(C60-1)") (class "Default")
      (node (ref "C60") (pin "P$1") (pinfunction "1_P$1") (pintype "bidirectional"))
      (node (ref "U1") (pin "B3") (pinfunction "VDDC_LV-CORE_LV_B3") (pintype "bidirectional"))
    )
    (net (code "78") (name "Net-(C71-2)") (class "Default")
      (node (ref "C71") (pin "P$2") (pinfunction "2_P$2") (pintype "bidirectional"))
      (node (ref "U1") (pin "B10") (pinfunction "LPMICBIAS_B10") (pintype "output"))
    )
    (net (code "79") (name "Net-(C78-1)") (class "Default")
      (node (ref "C78") (pin "P$1") (pinfunction "1_P$1") (pintype "bidirectional"))
      (node (ref "RZ11") (pin "1") (pinfunction "1_1") (pintype "passive"))
      (node (ref "VR2") (pin "1") (pinfunction "OUT_1") (pintype "power_in"))
    )
    (net (code "80") (name "Net-(C79-2)") (class "Default")
      (node (ref "C79") (pin "P$2") (pinfunction "2_P$2") (pintype "bidirectional"))
      (node (ref "U1") (pin "A12") (pinfunction "LPADC_VREF_A12") (pintype "bidirectional"))
    )
    (net (code "81") (name "Net-(C91-1)") (class "Default")
      (node (ref "C91") (pin "P$1") (pinfunction "1_P$1") (pintype "bidirectional"))
      (node (ref "RZ4") (pin "1") (pinfunction "1_1") (pintype "passive"))
      (node (ref "VR3") (pin "1") (pinfunction "OUT_1") (pintype "power_in"))
    )
    (net (code "82") (name "Net-(D1-PadA1)") (class "Default")
      (node (ref "D1") (pin "A1") (pinfunction "A1_A1") (pintype "bidirectional"))
      (node (ref "D1") (pin "A2") (pinfunction "A2_A2") (pintype "bidirectional"))
      (node (ref "D2") (pin "A1") (pinfunction "A1_A1") (pintype "bidirectional"))
      (node (ref "D2") (pin "A2") (pinfunction "A2_A2") (pintype "bidirectional"))
      (node (ref "JP1") (pin "1") (pinfunction "1_1") (pintype "passive"))
    )
    (net (code "83") (name "Net-(D1-PadC1)") (class "Default")
      (node (ref "D1") (pin "C1") (pinfunction "C1_C1") (pintype "bidirectional"))
      (node (ref "R5") (pin "1") (pinfunction "1_1") (pintype "passive"))
    )
    (net (code "84") (name "Net-(D1-PadC2)") (class "Default")
      (node (ref "D1") (pin "C2") (pinfunction "C2_C2") (pintype "bidirectional"))
      (node (ref "R2") (pin "1") (pinfunction "1_1") (pintype "passive"))
    )
    (net (code "85") (name "Net-(D2-PadC1)") (class "Default")
      (node (ref "D2") (pin "C1") (pinfunction "C1_C1") (pintype "bidirectional"))
      (node (ref "R4") (pin "1") (pinfunction "1_1") (pintype "passive"))
    )
    (net (code "86") (name "Net-(D2-PadC2)") (class "Default")
      (node (ref "D2") (pin "C2") (pinfunction "C2_C2") (pintype "bidirectional"))
      (node (ref "R3") (pin "1") (pinfunction "1_1") (pintype "passive"))
    )
    (net (code "87") (name "Net-(JP2-Pad1)") (class "Default")
      (node (ref "JP2") (pin "1") (pinfunction "1_1") (pintype "passive"))
      (node (ref "XR19") (pin "2") (pinfunction "2_2") (pintype "passive"))
    )
    (net (code "88") (name "Net-(L1-1)") (class "Default")
      (node (ref "L1") (pin "P$1") (pinfunction "1_P$1") (pintype "bidirectional"))
      (node (ref "VR1") (pin "2") (pinfunction "LX2_2") (pintype "bidirectional"))
    )
    (net (code "89") (name "Net-(L2-2)") (class "Default")
      (node (ref "L2") (pin "P$2") (pinfunction "2_P$2") (pintype "bidirectional"))
      (node (ref "VR1") (pin "8") (pinfunction "LX1_8") (pintype "bidirectional"))
    )
    (net (code "90") (name "Net-(L4-1)") (class "Default")
      (node (ref "C17") (pin "2") (pinfunction "2_2") (pintype "bidirectional"))
      (node (ref "C18") (pin "2") (pinfunction "2_2") (pintype "bidirectional"))
      (node (ref "C19") (pin "2") (pinfunction "2_2") (pintype "bidirectional"))
      (node (ref "L4") (pin "P$1") (pinfunction "1_P$1") (pintype "bidirectional"))
    )
    (net (code "91") (name "Net-(L4-2)") (class "Default")
      (node (ref "C10") (pin "2") (pinfunction "2_2") (pintype "bidirectional"))
      (node (ref "C16") (pin "2") (pinfunction "2_2") (pintype "bidirectional"))
      (node (ref "C21") (pin "2") (pinfunction "2_2") (pintype "bidirectional"))
      (node (ref "C39") (pin "2") (pinfunction "2_2") (pintype "bidirectional"))
      (node (ref "C9") (pin "2") (pinfunction "2_2") (pintype "bidirectional"))
      (node (ref "L4") (pin "P$2") (pinfunction "2_P$2") (pintype "bidirectional"))
      (node (ref "U4") (pin "19") (pinfunction "AC2_19") (pintype "bidirectional"))
    )
    (net (code "92") (name "Net-(L5-1)") (class "Default")
      (node (ref "L5") (pin "P$1") (pinfunction "1_P$1") (pintype "bidirectional"))
      (node (ref "U1") (pin "A1") (pinfunction "SIMOBUCK_SW_A1") (pintype "bidirectional"))
    )
    (net (code "93") (name "Net-(L5-2)") (class "Default")
      (node (ref "L5") (pin "P$2") (pinfunction "2_P$2") (pintype "bidirectional"))
      (node (ref "U1") (pin "A2") (pinfunction "SIMOBUCK_SWSEL_A2") (pintype "bidirectional"))
    )
    (net (code "94") (name "Net-(LS1-N)") (class "Default")
      (node (ref "D4") (pin "ANODE") (pinfunction "ANODE_ANODE") (pintype "bidirectional"))
      (node (ref "LS1") (pin "-") (pinfunction "N_-") (pintype "passive"))
      (node (ref "Q2") (pin "D") (pinfunction "D_D") (pintype "passive"))
    )
    (net (code "95") (name "Net-(R6-Pad1)") (class "Default")
      (node (ref "R6") (pin "1") (pinfunction "1_1") (pintype "passive"))
      (node (ref "R7") (pin "2") (pinfunction "2_2") (pintype "passive"))
    )
    (net (code "96") (name "Net-(R8-Pad2)") (class "Default")
      (node (ref "R8") (pin "2") (pinfunction "2_2") (pintype "passive"))
      (node (ref "R9") (pin "1") (pinfunction "1_1") (pintype "passive"))
    )
    (net (code "97") (name "Net-(R13-Pad1)") (class "Default")
      (node (ref "R13") (pin "1") (pinfunction "1_1") (pintype "passive"))
      (node (ref "R14") (pin "2") (pinfunction "2_2") (pintype "passive"))
    )
    (net (code "98") (name "Net-(R13-Pad2)") (class "Default")
      (node (ref "R13") (pin "2") (pinfunction "2_2") (pintype "passive"))
      (node (ref "RT1") (pin "1") (pinfunction "1_1") (pintype "passive"))
    )
    (net (code "99") (name "Net-(R18-Pad2)") (class "Default")
      (node (ref "R18") (pin "2") (pinfunction "2_2") (pintype "passive"))
      (node (ref "R23") (pin "1") (pinfunction "1_1") (pintype "passive"))
    )
    (net (code "100") (name "Net-(S3A-OUT)") (class "Default")
      (node (ref "C33") (pin "1") (pinfunction "1_1") (pintype "bidirectional"))
      (node (ref "RZ1") (pin "1") (pinfunction "1_1") (pintype "passive"))
      (node (ref "S3") (pin "8") (pinfunction "OUT_8") (pintype "bidirectional"))
    )
    (net (code "101") (name "Net-(S3B-OUT)") (class "Default")
      (node (ref "C25") (pin "1") (pinfunction "1_1") (pintype "bidirectional"))
      (node (ref "RZ2") (pin "1") (pinfunction "1_1") (pintype "passive"))
      (node (ref "S3") (pin "5") (pinfunction "OUT_5") (pintype "bidirectional"))
    )
    (net (code "102") (name "Net-(TP0-TESTPOINT)") (class "Default")
      (node (ref "TP0") (pin "P$1") (pinfunction "TESTPOINT_P$1") (pintype "bidirectional"))
      (node (ref "U2") (pin "C2") (pinfunction "GPIO0/RXOKLED_C2") (pintype "bidirectional"))
    )
    (net (code "103") (name "Net-(TP1-TESTPOINT)") (class "Default")
      (node (ref "TP1") (pin "P$1") (pinfunction "TESTPOINT_P$1") (pintype "bidirectional"))
      (node (ref "U2") (pin "D3") (pinfunction "GPIO1/SFDLED_D3") (pintype "bidirectional"))
    )
    (net (code "104") (name "Net-(TP2-TESTPOINT)") (class "Default")
      (node (ref "TP2") (pin "P$1") (pinfunction "TESTPOINT_P$1") (pintype "bidirectional"))
      (node (ref "U2") (pin "E4") (pinfunction "GPIO2/RXLED_E4") (pintype "bidirectional"))
    )
    (net (code "105") (name "Net-(TP3-TESTPOINT)") (class "Default")
      (node (ref "TP3") (pin "P$1") (pinfunction "TESTPOINT_P$1") (pintype "bidirectional"))
      (node (ref "U2") (pin "E2") (pinfunction "GPIO3/TXLED_E2") (pintype "bidirectional"))
    )
    (net (code "106") (name "Net-(TP4-TESTPOINT)") (class "Default")
      (node (ref "TP4") (pin "P$1") (pinfunction "TESTPOINT_P$1") (pintype "bidirectional"))
      (node (ref "U2") (pin "F1") (pinfunction "GPIO4/EXTPA_F1") (pintype "bidirectional"))
    )
    (net (code "107") (name "Net-(TP5-TESTPOINT)") (class "Default")
      (node (ref "TP5") (pin "P$1") (pinfunction "TESTPOINT_P$1") (pintype "bidirectional"))
      (node (ref "U2") (pin "D1") (pinfunction "GPIO5/EXTTXE/SPIPOL_D1") (pintype "bidirectional"))
    )
    (net (code "108") (name "Net-(U1-RFIOP)") (class "Default")
      (node (ref "CX5") (pin "1") (pinfunction "1_1") (pintype "passive"))
      (node (ref "L7") (pin "1") (pinfunction "1_1") (pintype "passive"))
      (node (ref "U1") (pin "M2") (pinfunction "RFIOP_M2") (pintype "bidirectional"))
    )
    (net (code "109") (name "Net-(U1-VDDBH_SW--BLE_BUCK_SW)") (class "Default")
      (node (ref "L6") (pin "1") (pinfunction "1_1") (pintype "bidirectional"))
      (node (ref "U1") (pin "H12") (pinfunction "VDDBH_SW--BLE_BUCK_SW_H12") (pintype "bidirectional"))
    )
    (net (code "110") (name "Net-(U1-XI)") (class "Default")
      (node (ref "C81") (pin "1") (pinfunction "1_1") (pintype "passive"))
      (node (ref "U1") (pin "A4") (pinfunction "XI_A4") (pintype "bidirectional"))
      (node (ref "X3") (pin "2") (pinfunction "2_2") (pintype "bidirectional"))
    )
    (net (code "111") (name "Net-(U1-XI32M)") (class "Default")
      (node (ref "CX4") (pin "1") (pinfunction "1_1") (pintype "passive"))
      (node (ref "U1") (pin "C12") (pinfunction "XI32M_C12") (pintype "bidirectional"))
      (node (ref "X1") (pin "3") (pinfunction "2_3") (pintype "bidirectional"))
    )
    (net (code "112") (name "Net-(U1-XO)") (class "Default")
      (node (ref "C80") (pin "1") (pinfunction "1_1") (pintype "passive"))
      (node (ref "U1") (pin "A5") (pinfunction "XO_A5") (pintype "bidirectional"))
      (node (ref "X3") (pin "1") (pinfunction "1_1") (pintype "bidirectional"))
    )
    (net (code "113") (name "Net-(U1-XO32M)") (class "Default")
      (node (ref "CX3") (pin "1") (pinfunction "1_1") (pintype "passive"))
      (node (ref "U1") (pin "D12") (pinfunction "XO32M_D12") (pintype "bidirectional"))
      (node (ref "X1") (pin "1") (pinfunction "1_1") (pintype "bidirectional"))
    )
    (net (code "114") (name "Net-(U2-RF2)") (class "Default")
      (node (ref "R1") (pin "1") (pinfunction "1_1") (pintype "passive"))
      (node (ref "U2") (pin "H5") (pinfunction "RF2_H5") (pintype "bidirectional"))
    )
    (net (code "115") (name "Net-(U2-VDD2A)") (class "Default")
      (node (ref "C12") (pin "P$1") (pinfunction "P$1_P$1") (pintype "bidirectional"))
      (node (ref "FB1") (pin "P$2") (pinfunction "P$2_P$2") (pintype "bidirectional"))
      (node (ref "U2") (pin "F15") (pinfunction "VDD2A_F15") (pintype "bidirectional"))
    )
    (net (code "116") (name "Net-(U2-VIO_D)") (class "Default")
      (node (ref "C23") (pin "1") (pinfunction "1_1") (pintype "bidirectional"))
      (node (ref "U2") (pin "A4") (pinfunction "VIO_D_A4") (pintype "bidirectional"))
    )
    (net (code "117") (name "Net-(U2-VTX_D)") (class "Default")
      (node (ref "C37") (pin "P$2") (pinfunction "P$2_P$2") (pintype "bidirectional"))
      (node (ref "U2") (pin "C14") (pinfunction "VTX_D_C14") (pintype "bidirectional"))
    )
    (net (code "118") (name "Net-(U2-XTI)") (class "Default")
      (node (ref "C3") (pin "P$1") (pinfunction "P$1_P$1") (pintype "bidirectional"))
      (node (ref "U2") (pin "H15") (pinfunction "XTI_H15") (pintype "bidirectional"))
      (node (ref "X4") (pin "1") (pinfunction "1_1") (pintype "bidirectional"))
    )
    (net (code "119") (name "Net-(U2-XTO)") (class "Default")
      (node (ref "C4") (pin "P$1") (pinfunction "P$1_P$1") (pintype "bidirectional"))
      (node (ref "U2") (pin "G14") (pinfunction "XTO_G14") (pintype "bidirectional"))
      (node (ref "X4") (pin "3") (pinfunction "2_3") (pintype "bidirectional"))
    )
    (net (code "120") (name "Net-(U3-ISET)") (class "Default")
      (node (ref "R15") (pin "2") (pinfunction "2_2") (pintype "passive"))
      (node (ref "U3") (pin "2") (pinfunction "ISET_2") (pintype "bidirectional"))
    )
    (net (code "121") (name "Net-(U3-PRETERM)") (class "Default")
      (node (ref "RX7") (pin "2") (pinfunction "2_2") (pintype "passive"))
      (node (ref "U3") (pin "4") (pinfunction "PRETERM_4") (pintype "bidirectional"))
    )
    (net (code "122") (name "Net-(U4-AC1)") (class "Default")
      (node (ref "C10") (pin "1") (pinfunction "1_1") (pintype "bidirectional"))
      (node (ref "C15") (pin "2") (pinfunction "2_2") (pintype "bidirectional"))
      (node (ref "C17") (pin "1") (pinfunction "1_1") (pintype "bidirectional"))
      (node (ref "C18") (pin "1") (pinfunction "1_1") (pintype "bidirectional"))
      (node (ref "C19") (pin "1") (pinfunction "1_1") (pintype "bidirectional"))
      (node (ref "C20") (pin "2") (pinfunction "2_2") (pintype "bidirectional"))
      (node (ref "C38") (pin "2") (pinfunction "2_2") (pintype "bidirectional"))
      (node (ref "C9") (pin "1") (pinfunction "1_1") (pintype "bidirectional"))
      (node (ref "U4") (pin "2") (pinfunction "AC1_2") (pintype "bidirectional"))
    )
    (net (code "123") (name "Net-(U4-BOOT1)") (class "Default")
      (node (ref "C15") (pin "1") (pinfunction "1_1") (pintype "bidirectional"))
      (node (ref "U4") (pin "3") (pinfunction "BOOT1_3") (pintype "bidirectional"))
    )
    (net (code "124") (name "Net-(U4-BOOT2)") (class "Default")
      (node (ref "C16") (pin "1") (pinfunction "1_1") (pintype "bidirectional"))
      (node (ref "U4") (pin "17") (pinfunction "BOOT2_17") (pintype "bidirectional"))
    )
    (net (code "125") (name "Net-(U4-CLAMP1)") (class "Default")
      (node (ref "C38") (pin "1") (pinfunction "1_1") (pintype "bidirectional"))
      (node (ref "U4") (pin "5") (pinfunction "CLAMP1_5") (pintype "bidirectional"))
    )
    (net (code "126") (name "Net-(U4-CLAMP2)") (class "Default")
      (node (ref "C39") (pin "1") (pinfunction "1_1") (pintype "bidirectional"))
      (node (ref "U4") (pin "16") (pinfunction "CLAMP2_16") (pintype "bidirectional"))
    )
    (net (code "127") (name "Net-(U4-COMM1)") (class "Default")
      (node (ref "C20") (pin "1") (pinfunction "1_1") (pintype "bidirectional"))
      (node (ref "U4") (pin "6") (pinfunction "COMM1_6") (pintype "bidirectional"))
    )
    (net (code "128") (name "Net-(U4-COMM2)") (class "Default")
      (node (ref "C21") (pin "1") (pinfunction "1_1") (pintype "bidirectional"))
      (node (ref "U4") (pin "15") (pinfunction "COMM2_15") (pintype "bidirectional"))
    )
    (net (code "129") (name "Net-(U4-FOD)") (class "Default")
      (node (ref "R23") (pin "2") (pinfunction "2_2") (pintype "passive"))
      (node (ref "R7") (pin "1") (pinfunction "1_1") (pintype "passive"))
      (node (ref "R9") (pin "2") (pinfunction "2_2") (pintype "passive"))
      (node (ref "U4") (pin "14") (pinfunction "FOD_14") (pintype "bidirectional"))
    )
    (net (code "130") (name "Net-(U4-ILIM)") (class "Default")
      (node (ref "R8") (pin "1") (pinfunction "1_1") (pintype "passive"))
      (node (ref "U4") (pin "12") (pinfunction "ILIM_12") (pintype "bidirectional"))
    )
    (net (code "131") (name "Net-(U4-RECT)") (class "Default")
      (node (ref "C28") (pin "1") (pinfunction "1_1") (pintype "bidirectional"))
      (node (ref "C56") (pin "1") (pinfunction "1_1") (pintype "bidirectional"))
      (node (ref "C57") (pin "1") (pinfunction "1_1") (pintype "bidirectional"))
      (node (ref "R18") (pin "1") (pinfunction "1_1") (pintype "passive"))
      (node (ref "U4") (pin "18") (pinfunction "RECT_18") (pintype "bidirectional"))
    )
    (net (code "132") (name "Net-(U6-CAP)") (class "Default")
      (node (ref "C36") (pin "1") (pinfunction "1_1") (pintype "bidirectional"))
      (node (ref "U6") (pin "9") (pinfunction "CAP_9") (pintype "bidirectional"))
    )
    (net (code "133") (name "Net-(U6-PS1)") (class "Default")
      (node (ref "RX9") (pin "2") (pinfunction "2_2") (pintype "passive"))
      (node (ref "RZ12") (pin "1") (pinfunction "1_1") (pintype "passive"))
      (node (ref "U6") (pin "5") (pinfunction "PS1_5") (pintype "input"))
    )
    (net (code "134") (name "Net-(U7-VCTRL)") (class "Default")
      (node (ref "JP3") (pin "2") (pinfunction "2_2") (pintype "passive"))
      (node (ref "U7") (pin "8") (pinfunction "VCTRL_8") (pintype "bidirectional"))
    )
    (net (code "135") (name "Net-(U7-VDD)") (class "Default")
      (node (ref "C11") (pin "P$1") (pinfunction "P$1_P$1") (pintype "bidirectional"))
      (node (ref "C43") (pin "P$1") (pinfunction "P$1_P$1") (pintype "bidirectional"))
      (node (ref "RZ4") (pin "2") (pinfunction "2_2") (pintype "passive"))
      (node (ref "U7") (pin "1") (pinfunction "VDD_1") (pintype "bidirectional"))
    )
    (net (code "136") (name "Net-(VR2-EN)") (class "Default")
      (node (ref "RZ10") (pin "2") (pinfunction "2_2") (pintype "passive"))
      (node (ref "VR2") (pin "3") (pinfunction "EN_3") (pintype "input"))
    )
    (net (code "137") (name "Net-(XJ1-CC1)") (class "Default")
      (node (ref "XJ1") (pin "A5") (pinfunction "CC1_A5") (pintype "bidirectional"))
      (node (ref "XR16") (pin "1") (pinfunction "1_1") (pintype "passive"))
    )
    (net (code "138") (name "Net-(XJ1-CC2)") (class "Default")
      (node (ref "XJ1") (pin "B5") (pinfunction "CC2_B5") (pintype "bidirectional"))
      (node (ref "XR17") (pin "1") (pinfunction "1_1") (pintype "passive"))
    )
    (net (code "139") (name "RF1") (class "Default")
      (node (ref "S2") (pin "9") (pinfunction "J2_9") (pintype "bidirectional"))
      (node (ref "U7") (pin "6") (pinfunction "LNA_OUT_6") (pintype "bidirectional"))
    )
    (net (code "140") (name "RF2") (class "Default")
      (node (ref "A2") (pin "FEED") (pinfunction "ANTENNA_FEED") (pintype "bidirectional"))
      (node (ref "S2") (pin "3") (pinfunction "J3_3") (pintype "bidirectional"))
    )
    (net (code "141") (name "RF3") (class "Default")
      (node (ref "A3") (pin "FEED") (pinfunction "ANTENNA_FEED") (pintype "bidirectional"))
      (node (ref "S2") (pin "1") (pinfunction "J1_1") (pintype "bidirectional"))
      (node (ref "S4") (pin "IN") (pinfunction "IN_IN") (pintype "bidirectional"))
      (node (ref "S4") (pin "OUT") (pinfunction "A_OUT") (pintype "bidirectional"))
    )
    (net (code "142") (name "VBAT") (class "Default")
      (node (ref "C42") (pin "1") (pinfunction "1_1") (pintype "bidirectional"))
      (node (ref "J4") (pin "3") (pinfunction "3_3") (pintype "bidirectional"))
      (node (ref "J4") (pin "3SUPP") (pinfunction "3_3SUPP") (pintype "bidirectional"))
      (node (ref "JP9") (pin "1") (pinfunction "1_1") (pintype "passive"))
      (node (ref "S1") (pin "2") (pinfunction "2_2") (pintype "passive"))
      (node (ref "U3") (pin "10") (pinfunction "OUT_10") (pintype "bidirectional"))
    )
    (net (code "143") (name "VBAT_SWITCHED") (class "Default")
      (node (ref "C45") (pin "2") (pinfunction "2_2") (pintype "bidirectional"))
      (node (ref "C48") (pin "1") (pinfunction "1_1") (pintype "bidirectional"))
      (node (ref "R31") (pin "2") (pinfunction "2_2") (pintype "passive"))
      (node (ref "R33") (pin "1") (pinfunction "1_1") (pintype "passive"))
      (node (ref "R34") (pin "1") (pinfunction "1_1") (pintype "passive"))
      (node (ref "S1") (pin "3") (pinfunction "3_3") (pintype "passive"))
      (node (ref "VR1") (pin "1") (pinfunction "VIN2_1") (pintype "bidirectional"))
      (node (ref "VR1") (pin "7") (pinfunction "VIN1_7") (pintype "bidirectional"))
    )
    (net (code "144") (name "VDDAUDA_1P8-CLEAN") (class "Default")
      (node (ref "C72") (pin "P$1") (pinfunction "1_P$1") (pintype "bidirectional"))
      (node (ref "RZ11") (pin "2") (pinfunction "2_2") (pintype "passive"))
      (node (ref "U1") (pin "B11") (pinfunction "VDDAUDA_B11") (pintype "bidirectional"))
    )
    (net (code "145") (name "VQI") (class "Default")
      (node (ref "C29") (pin "1") (pinfunction "1_1") (pintype "bidirectional"))
      (node (ref "C41") (pin "1") (pinfunction "1_1") (pintype "bidirectional"))
      (node (ref "C53") (pin "1") (pinfunction "1_1") (pintype "bidirectional"))
      (node (ref "Q1") (pin "A2") (pinfunction "D1_A2") (pintype "bidirectional"))
      (node (ref "Q1") (pin "A3") (pinfunction "D1_A3") (pintype "bidirectional"))
      (node (ref "Q1") (pin "B3") (pinfunction "D1_B3") (pintype "bidirectional"))
      (node (ref "U3") (pin "1") (pinfunction "IN_1") (pintype "bidirectional"))
      (node (ref "U4") (pin "4") (pinfunction "OUT_4") (pintype "bidirectional"))
    )
    (net (code "146") (name "VR1_1P8_EN") (class "Default")
      (node (ref "R34") (pin "2") (pinfunction "2_2") (pintype "passive"))
      (node (ref "VR1") (pin "6") (pinfunction "EN1_6") (pintype "bidirectional"))
    )
    (net (code "147") (name "VR1_2P5_EN") (class "Default")
      (node (ref "R33") (pin "2") (pinfunction "2_2") (pintype "passive"))
      (node (ref "VR1") (pin "12") (pinfunction "EN2_12") (pintype "bidirectional"))
    )
    (net (code "148") (name "VUSB") (class "Default")
      (node (ref "C40") (pin "2") (pinfunction "2_2") (pintype "bidirectional"))
      (node (ref "Q1") (pin "B2") (pinfunction "D2_B2") (pintype "bidirectional"))
      (node (ref "Q1") (pin "C2") (pinfunction "D2_C2") (pintype "bidirectional"))
      (node (ref "Q1") (pin "C3") (pinfunction "D2_C3") (pintype "bidirectional"))
      (node (ref "U4") (pin "9") (pinfunction "AD_9") (pintype "bidirectional"))
      (node (ref "XJ1") (pin "A4/B9") (pinfunction "VBUS_A4/B9") (pintype "power_in"))
      (node (ref "XJ1") (pin "B4/A9") (pinfunction "VBUS_B4/A9") (pintype "power_in"))
    )
    (net (code "149") (name "unconnected-(Q1-S-PadB1)") (class "Default")
      (node (ref "Q1") (pin "B1") (pinfunction "S_B1") (pintype "bidirectional"))
    )
    (net (code "150") (name "unconnected-(S1-Pad1)") (class "Default")
      (node (ref "S1") (pin "1") (pinfunction "1_1") (pintype "passive"))
    )
    (net (code "151") (name "unconnected-(U1-GPIO0-PadH3)") (class "Default")
      (node (ref "U1") (pin "H3") (pinfunction "GPIO0_H3") (pintype "bidirectional"))
    )
    (net (code "152") (name "unconnected-(U1-GPIO1-PadJ4)") (class "Default")
      (node (ref "U1") (pin "J4") (pinfunction "GPIO1_J4") (pintype "bidirectional"))
    )
    (net (code "153") (name "unconnected-(U1-GPIO2-PadK4)") (class "Default")
      (node (ref "U1") (pin "K4") (pinfunction "GPIO2_K4") (pintype "bidirectional"))
    )
    (net (code "154") (name "unconnected-(U1-GPIO4-PadM4)") (class "Default")
      (node (ref "U1") (pin "M4") (pinfunction "GPIO4_M4") (pintype "bidirectional"))
    )
    (net (code "155") (name "unconnected-(U1-GPIO5-PadH4)") (class "Default")
      (node (ref "U1") (pin "H4") (pinfunction "GPIO5_H4") (pintype "bidirectional"))
    )
    (net (code "156") (name "unconnected-(U1-GPIO7-PadJ6)") (class "Default")
      (node (ref "U1") (pin "J6") (pinfunction "GPIO7_J6") (pintype "bidirectional"))
    )
    (net (code "157") (name "unconnected-(U1-GPIO11-PadE4)") (class "Default")
      (node (ref "U1") (pin "E4") (pinfunction "GPIO11_E4") (pintype "bidirectional"))
    )
    (net (code "158") (name "unconnected-(U1-GPIO12-PadB4)") (class "Default")
      (node (ref "U1") (pin "B4") (pinfunction "GPIO12_B4") (pintype "bidirectional"))
    )
    (net (code "159") (name "unconnected-(U1-GPIO15-PadE5)") (class "Default")
      (node (ref "U1") (pin "E5") (pinfunction "GPIO15_E5") (pintype "bidirectional"))
    )
    (net (code "160") (name "unconnected-(U1-GPIO16-PadD7)") (class "Default")
      (node (ref "U1") (pin "D7") (pinfunction "GPIO16_D7") (pintype "bidirectional"))
    )
    (net (code "161") (name "unconnected-(U1-GPIO19-PadC3)") (class "Default")
      (node (ref "U1") (pin "C3") (pinfunction "GPIO19_C3") (pintype "bidirectional"))
    )
    (net (code "162") (name "unconnected-(U1-GPIO22-PadF3)") (class "Default")
      (node (ref "U1") (pin "F3") (pinfunction "GPIO22_F3") (pintype "bidirectional"))
    )
    (net (code "163") (name "unconnected-(U1-GPIO23-PadF2)") (class "Default")
      (node (ref "U1") (pin "F2") (pinfunction "GPIO23_F2") (pintype "bidirectional"))
    )
    (net (code "164") (name "unconnected-(U1-GPIO28-PadE3)") (class "Default")
      (node (ref "U1") (pin "E3") (pinfunction "GPIO28_E3") (pintype "bidirectional"))
    )
    (net (code "165") (name "unconnected-(U1-GPIO29-PadF4)") (class "Default")
      (node (ref "U1") (pin "F4") (pinfunction "GPIO29_F4") (pintype "bidirectional"))
    )
    (net (code "166") (name "unconnected-(U1-GPIO37-PadF11)") (class "Default")
      (node (ref "U1") (pin "F11") (pinfunction "GPIO37_F11") (pintype "bidirectional"))
    )
    (net (code "167") (name "unconnected-(U1-GPIO52-PadC10)") (class "Default")
      (node (ref "U1") (pin "C10") (pinfunction "GPIO52_C10") (pintype "bidirectional"))
    )
    (net (code "168") (name "unconnected-(U1-GPIO54-PadD10)") (class "Default")
      (node (ref "U1") (pin "D10") (pinfunction "GPIO54_D10") (pintype "bidirectional"))
    )
    (net (code "169") (name "unconnected-(U1-GPIO56-PadE10)") (class "Default")
      (node (ref "U1") (pin "E10") (pinfunction "GPIO56_E10") (pintype "bidirectional"))
    )
    (net (code "170") (name "unconnected-(U1-GPIO57-PadE9)") (class "Default")
      (node (ref "U1") (pin "E9") (pinfunction "GPIO57_E9") (pintype "bidirectional"))
    )
    (net (code "171") (name "unconnected-(U1-GPIO59-PadJ8)") (class "Default")
      (node (ref "U1") (pin "J8") (pinfunction "GPIO59_J8") (pintype "bidirectional"))
    )
    (net (code "172") (name "unconnected-(U1-GPIO61-PadK6)") (class "Default")
      (node (ref "U1") (pin "K6") (pinfunction "GPIO61_K6") (pintype "bidirectional"))
    )
    (net (code "173") (name "unconnected-(U1-GPIO62-PadL6)") (class "Default")
      (node (ref "U1") (pin "L6") (pinfunction "GPIO62_L6") (pintype "bidirectional"))
    )
    (net (code "174") (name "unconnected-(U1-GPIO64-PadB6)") (class "Default")
      (node (ref "U1") (pin "B6") (pinfunction "GPIO64_B6") (pintype "bidirectional"))
    )
    (net (code "175") (name "unconnected-(U1-GPIO67-PadC6)") (class "Default")
      (node (ref "U1") (pin "C6") (pinfunction "GPIO67_C6") (pintype "bidirectional"))
    )
    (net (code "176") (name "unconnected-(U1-GPIO68-PadB7)") (class "Default")
      (node (ref "U1") (pin "B7") (pinfunction "GPIO68_B7") (pintype "bidirectional"))
    )
    (net (code "177") (name "unconnected-(U1-GPIO70-PadC5)") (class "Default")
      (node (ref "U1") (pin "C5") (pinfunction "GPIO70_C5") (pintype "bidirectional"))
    )
    (net (code "178") (name "unconnected-(U1-GPIO71-PadC7)") (class "Default")
      (node (ref "U1") (pin "C7") (pinfunction "GPIO71_C7") (pintype "bidirectional"))
    )
    (net (code "179") (name "unconnected-(U1-GPIO73-PadD8)") (class "Default")
      (node (ref "U1") (pin "D8") (pinfunction "GPIO73_D8") (pintype "bidirectional"))
    )
    (net (code "180") (name "unconnected-(U1-GPIO74-PadG11)") (class "Default")
      (node (ref "U1") (pin "G11") (pinfunction "GPIO74_G11") (pintype "bidirectional"))
    )
    (net (code "181") (name "unconnected-(U1-GPIO75-PadH11)") (class "Default")
      (node (ref "U1") (pin "H11") (pinfunction "GPIO75_H11") (pintype "bidirectional"))
    )
    (net (code "182") (name "unconnected-(U1-GPIO76-PadJ11)") (class "Default")
      (node (ref "U1") (pin "J11") (pinfunction "GPIO76_J11") (pintype "bidirectional"))
    )
    (net (code "183") (name "unconnected-(U1-GPIO77-PadK11)") (class "Default")
      (node (ref "U1") (pin "K11") (pinfunction "GPIO77_K11") (pintype "bidirectional"))
    )
    (net (code "184") (name "unconnected-(U1-GPIO78-PadL11)") (class "Default")
      (node (ref "U1") (pin "L11") (pinfunction "GPIO78_L11") (pintype "bidirectional"))
    )
    (net (code "185") (name "unconnected-(U1-GPIO84-PadJ9)") (class "Default")
      (node (ref "U1") (pin "J9") (pinfunction "GPIO84_J9") (pintype "bidirectional"))
    )
    (net (code "186") (name "unconnected-(U1-GPIO85-PadH9)") (class "Default")
      (node (ref "U1") (pin "H9") (pinfunction "GPIO85_H9") (pintype "bidirectional"))
    )
    (net (code "187") (name "unconnected-(U1-GPIO86-PadG10)") (class "Default")
      (node (ref "U1") (pin "G10") (pinfunction "GPIO86_G10") (pintype "bidirectional"))
    )
    (net (code "188") (name "unconnected-(U1-GPIO87-PadG9)") (class "Default")
      (node (ref "U1") (pin "G9") (pinfunction "GPIO87_G9") (pintype "bidirectional"))
    )
    (net (code "189") (name "unconnected-(U1-GPIO89-PadF10)") (class "Default")
      (node (ref "U1") (pin "F10") (pinfunction "GPIO89_F10") (pintype "bidirectional"))
    )
    (net (code "190") (name "unconnected-(U1-GPIO90-PadJ2)") (class "Default")
      (node (ref "U1") (pin "J2") (pinfunction "GPIO90_J2") (pintype "bidirectional"))
    )
    (net (code "191") (name "unconnected-(U1-GPIO91-PadK2)") (class "Default")
      (node (ref "U1") (pin "K2") (pinfunction "GPIO91_K2") (pintype "bidirectional"))
    )
    (net (code "192") (name "unconnected-(U1-LPADC_D0NSE0-PadA10)") (class "Default")
      (node (ref "U1") (pin "A10") (pinfunction "LPADC_D0NSE0_A10") (pintype "input"))
    )
    (net (code "193") (name "unconnected-(U1-LPADC_D0PSE1-PadA11)") (class "Default")
      (node (ref "U1") (pin "A11") (pinfunction "LPADC_D0PSE1_A11") (pintype "input"))
    )
    (net (code "194") (name "unconnected-(U1-LPADC_D1NSE2-PadC11)") (class "Default")
      (node (ref "U1") (pin "C11") (pinfunction "LPADC_D1NSE2_C11") (pintype "input"))
    )
    (net (code "195") (name "unconnected-(U1-LPADC_D1PSE3-PadD11)") (class "Default")
      (node (ref "U1") (pin "D11") (pinfunction "LPADC_D1PSE3_D11") (pintype "input"))
    )
    (net (code "196") (name "unconnected-(U1-MIPI_CLKN-PadJ12)") (class "Default")
      (node (ref "U1") (pin "J12") (pinfunction "MIPI_CLKN_J12") (pintype "bidirectional"))
    )
    (net (code "197") (name "unconnected-(U1-MIPI_CLKP-PadK12)") (class "Default")
      (node (ref "U1") (pin "K12") (pinfunction "MIPI_CLKP_K12") (pintype "bidirectional"))
    )
    (net (code "198") (name "unconnected-(U1-MIPI_DON-PadL12)") (class "Default")
      (node (ref "U1") (pin "L12") (pinfunction "MIPI_DON_L12") (pintype "bidirectional"))
    )
    (net (code "199") (name "unconnected-(U1-MIPI_DOP-PadM12)") (class "Default")
      (node (ref "U1") (pin "M12") (pinfunction "MIPI_DOP_M12") (pintype "bidirectional"))
    )
    (net (code "200") (name "unconnected-(U1-TXEN-PadK1)") (class "Default")
      (node (ref "U1") (pin "K1") (pinfunction "TXEN_K1") (pintype "output"))
    )
    (net (code "201") (name "unconnected-(VR1-NC1-Pad5)") (class "Default")
      (node (ref "VR1") (pin "5") (pinfunction "NC1_5") (pintype "bidirectional"))
    )
    (net (code "202") (name "unconnected-(VR1-NC2-Pad11)") (class "Default")
      (node (ref "VR1") (pin "11") (pinfunction "NC2_11") (pintype "bidirectional"))
    )
    (net (code "203") (name "unconnected-(XJ1-SBU1-PadA8)") (class "Default")
      (node (ref "XJ1") (pin "A8") (pinfunction "SBU1_A8") (pintype "bidirectional"))
    )
    (net (code "204") (name "unconnected-(XJ1-SBU2-PadB8)") (class "Default")
      (node (ref "XJ1") (pin "B8") (pinfunction "SBU2_B8") (pintype "bidirectional"))
    )
    (net (code "205") (name "~{AD_EN}") (class "Default")
      (node (ref "Q1") (pin "A1") (pinfunction "G1_A1") (pintype "input"))
      (node (ref "Q1") (pin "C1") (pinfunction "G2_C1") (pintype "input"))
      (node (ref "U4") (pin "8") (pinfunction "~{AD-EN}_8") (pintype "bidirectional"))
    )
  )
)
